# M840K.net
KiCad netlist of a schematic drawn in EAGLE
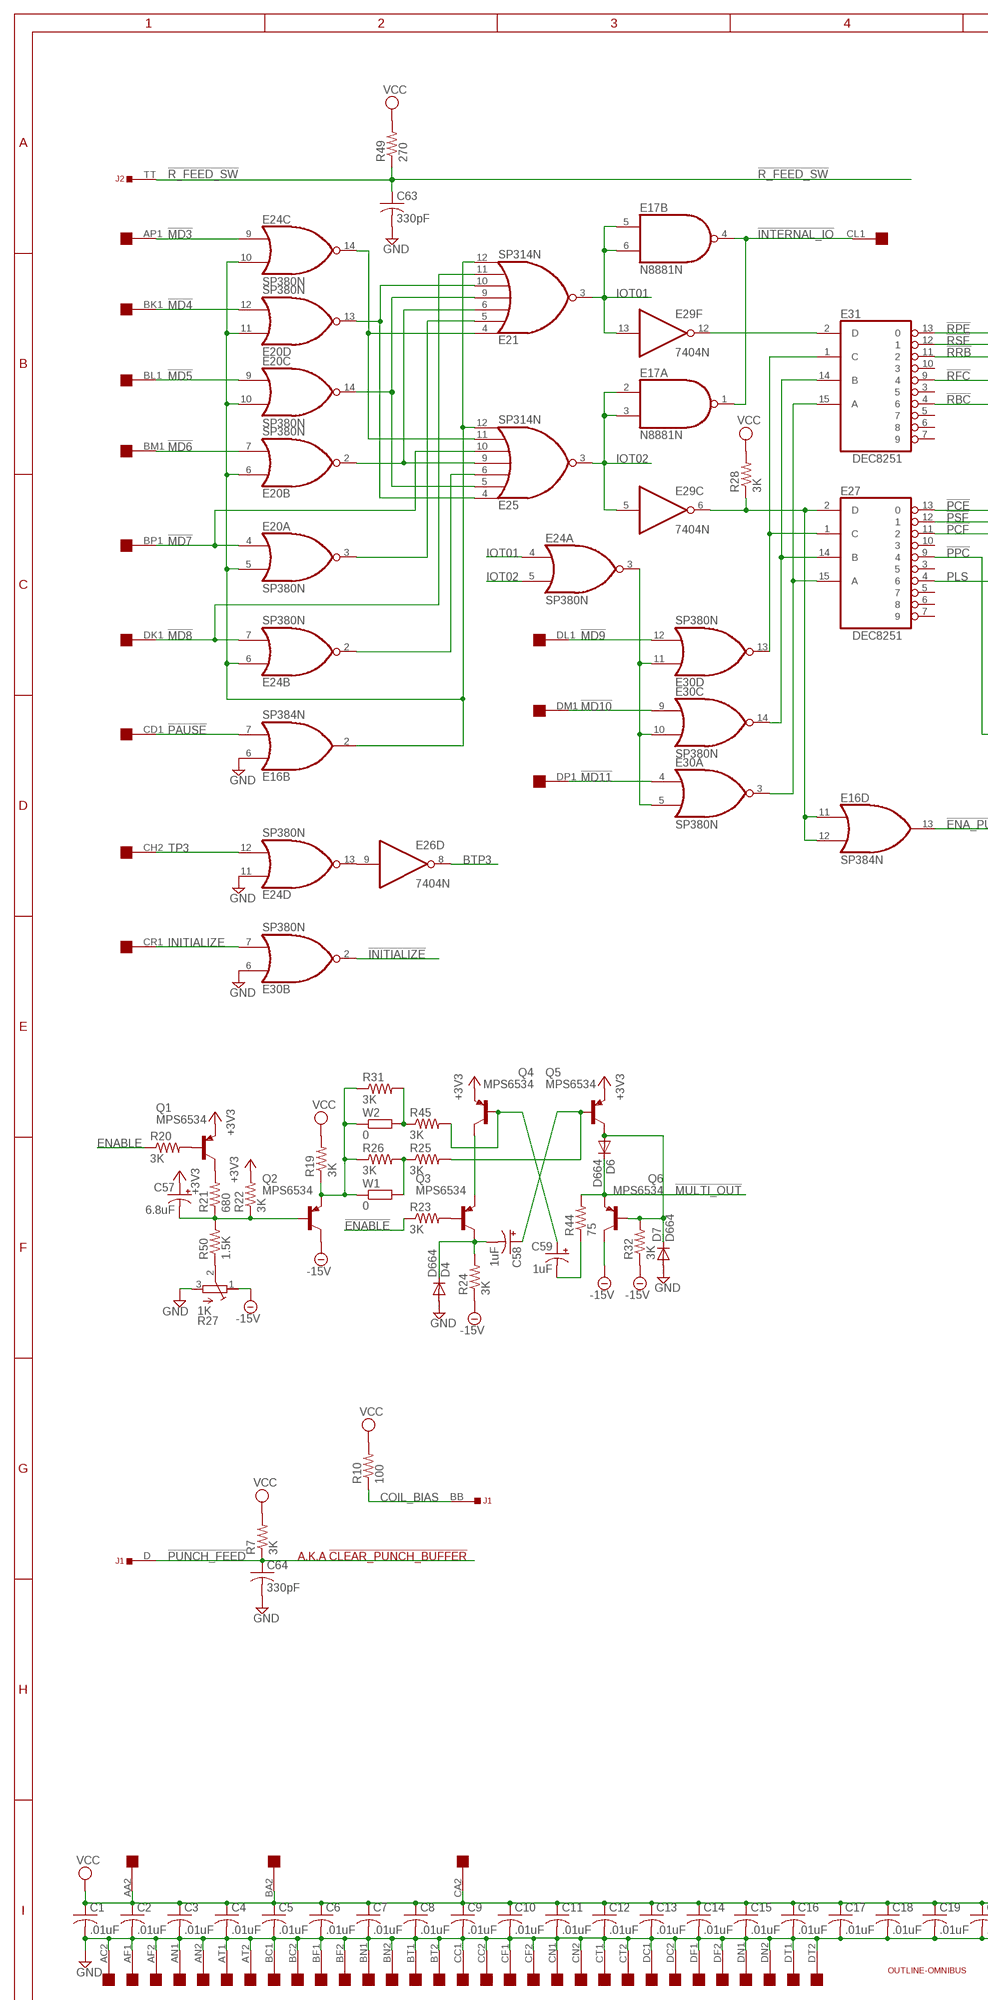
[diagram p0: schematic, sheet 1, part 1 of 2]
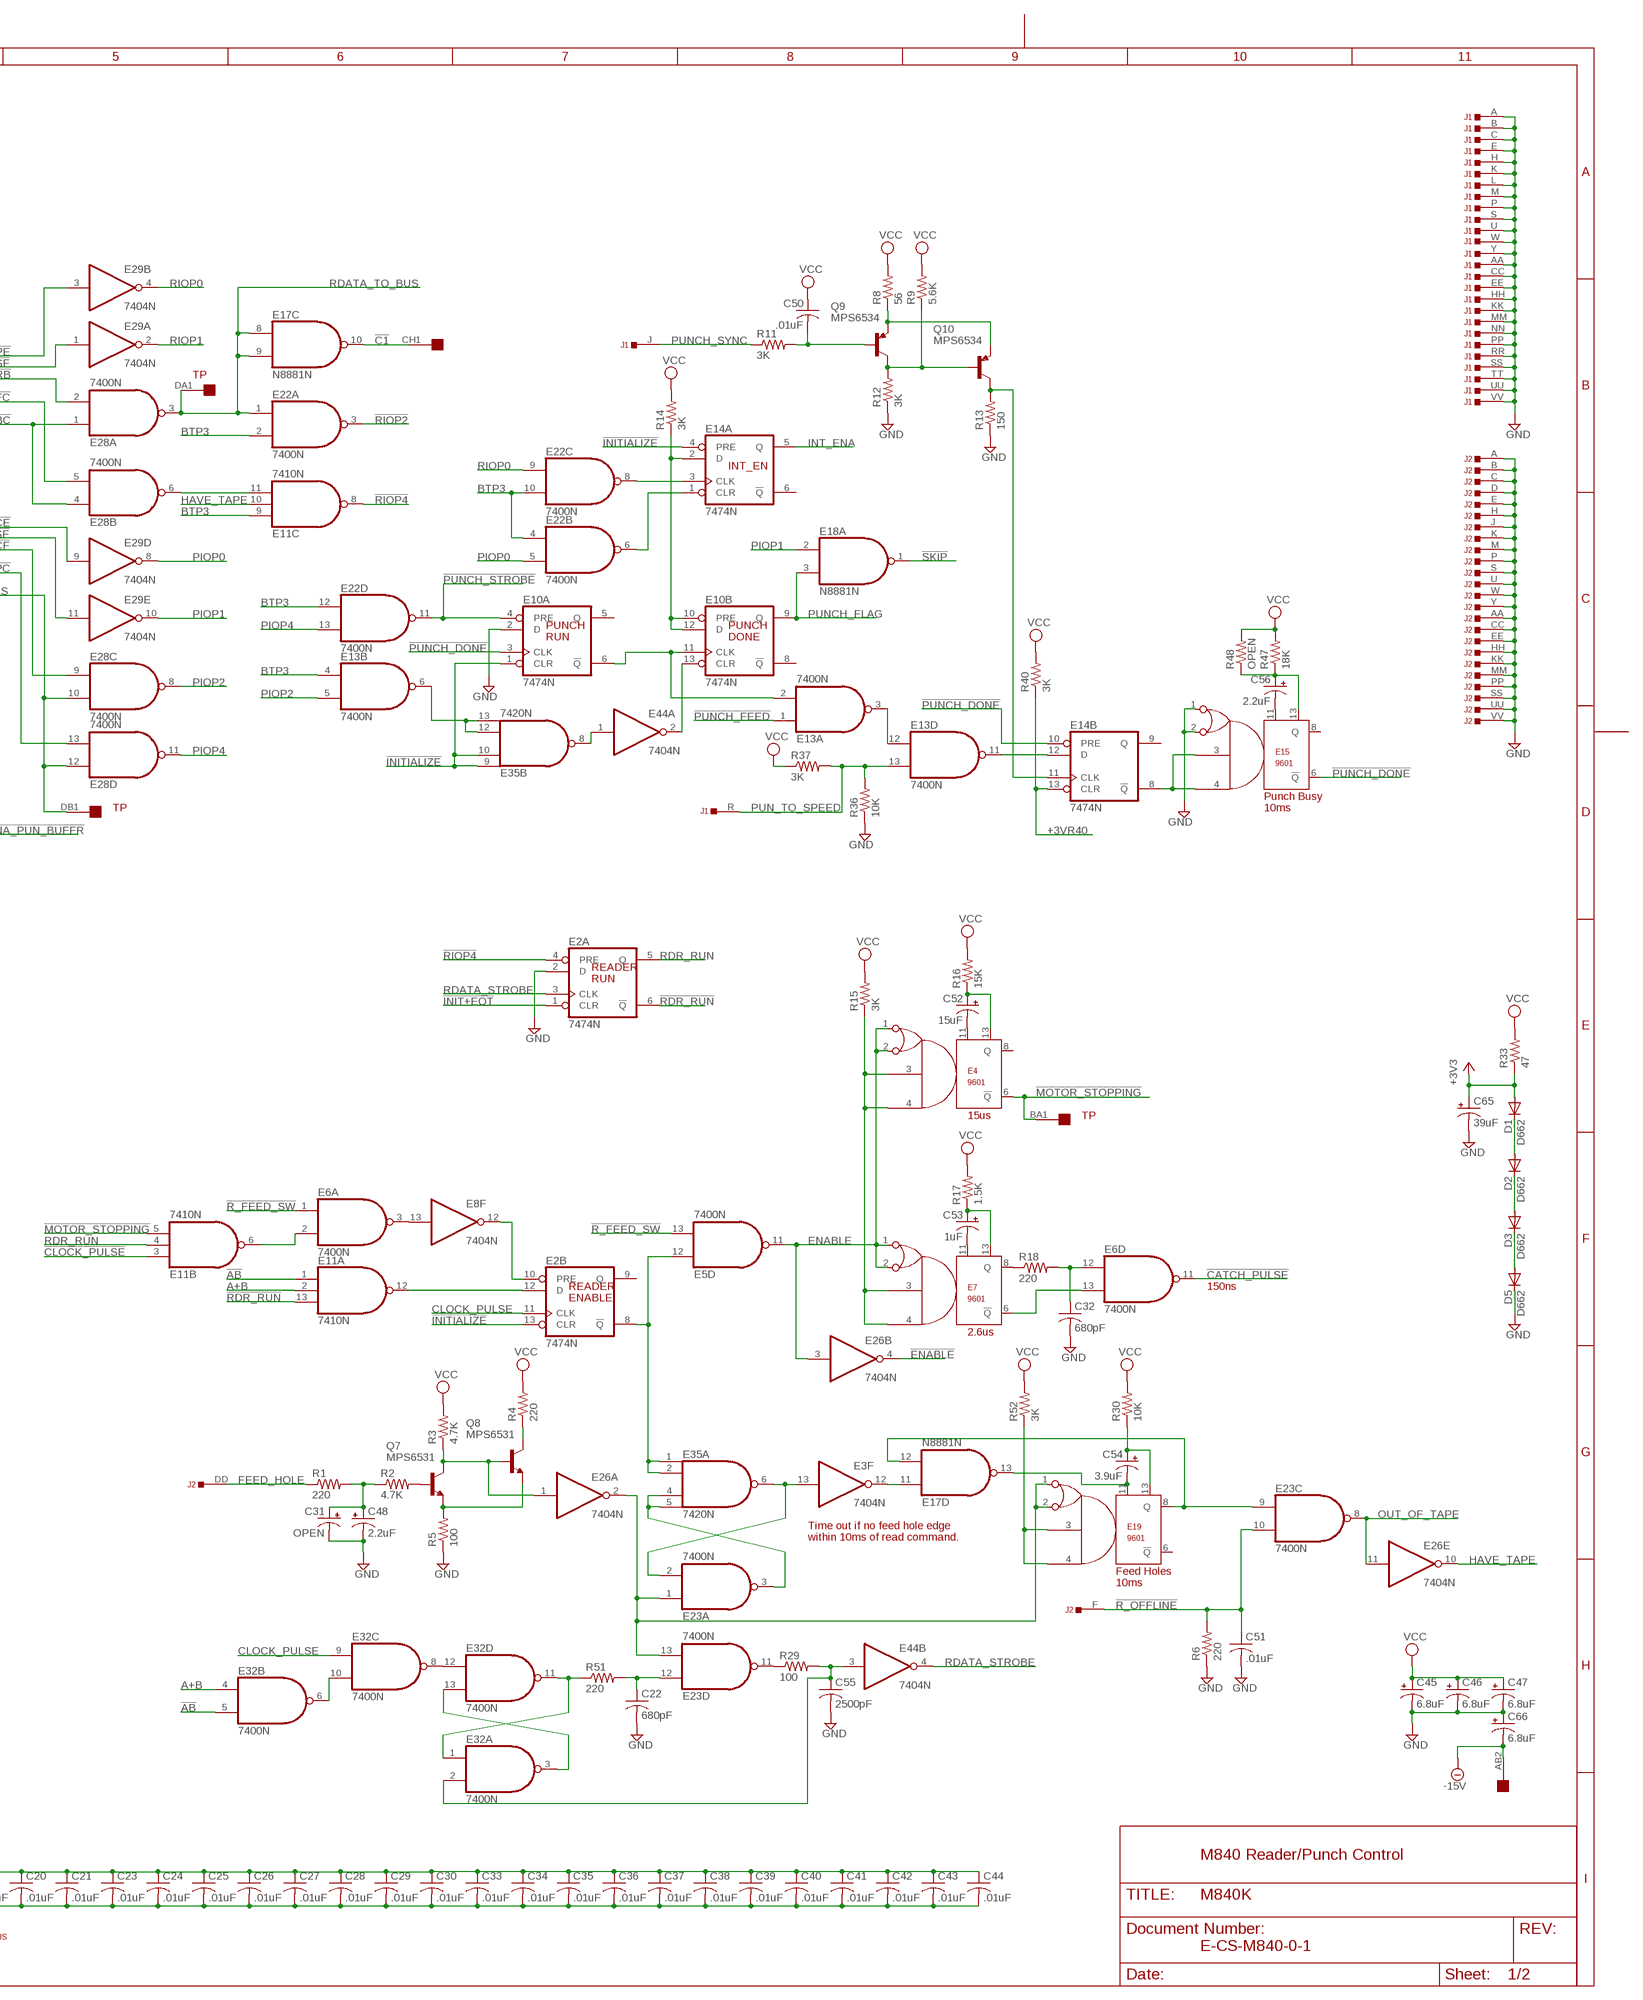
[diagram p1: schematic, sheet 1, part 2 of 2]
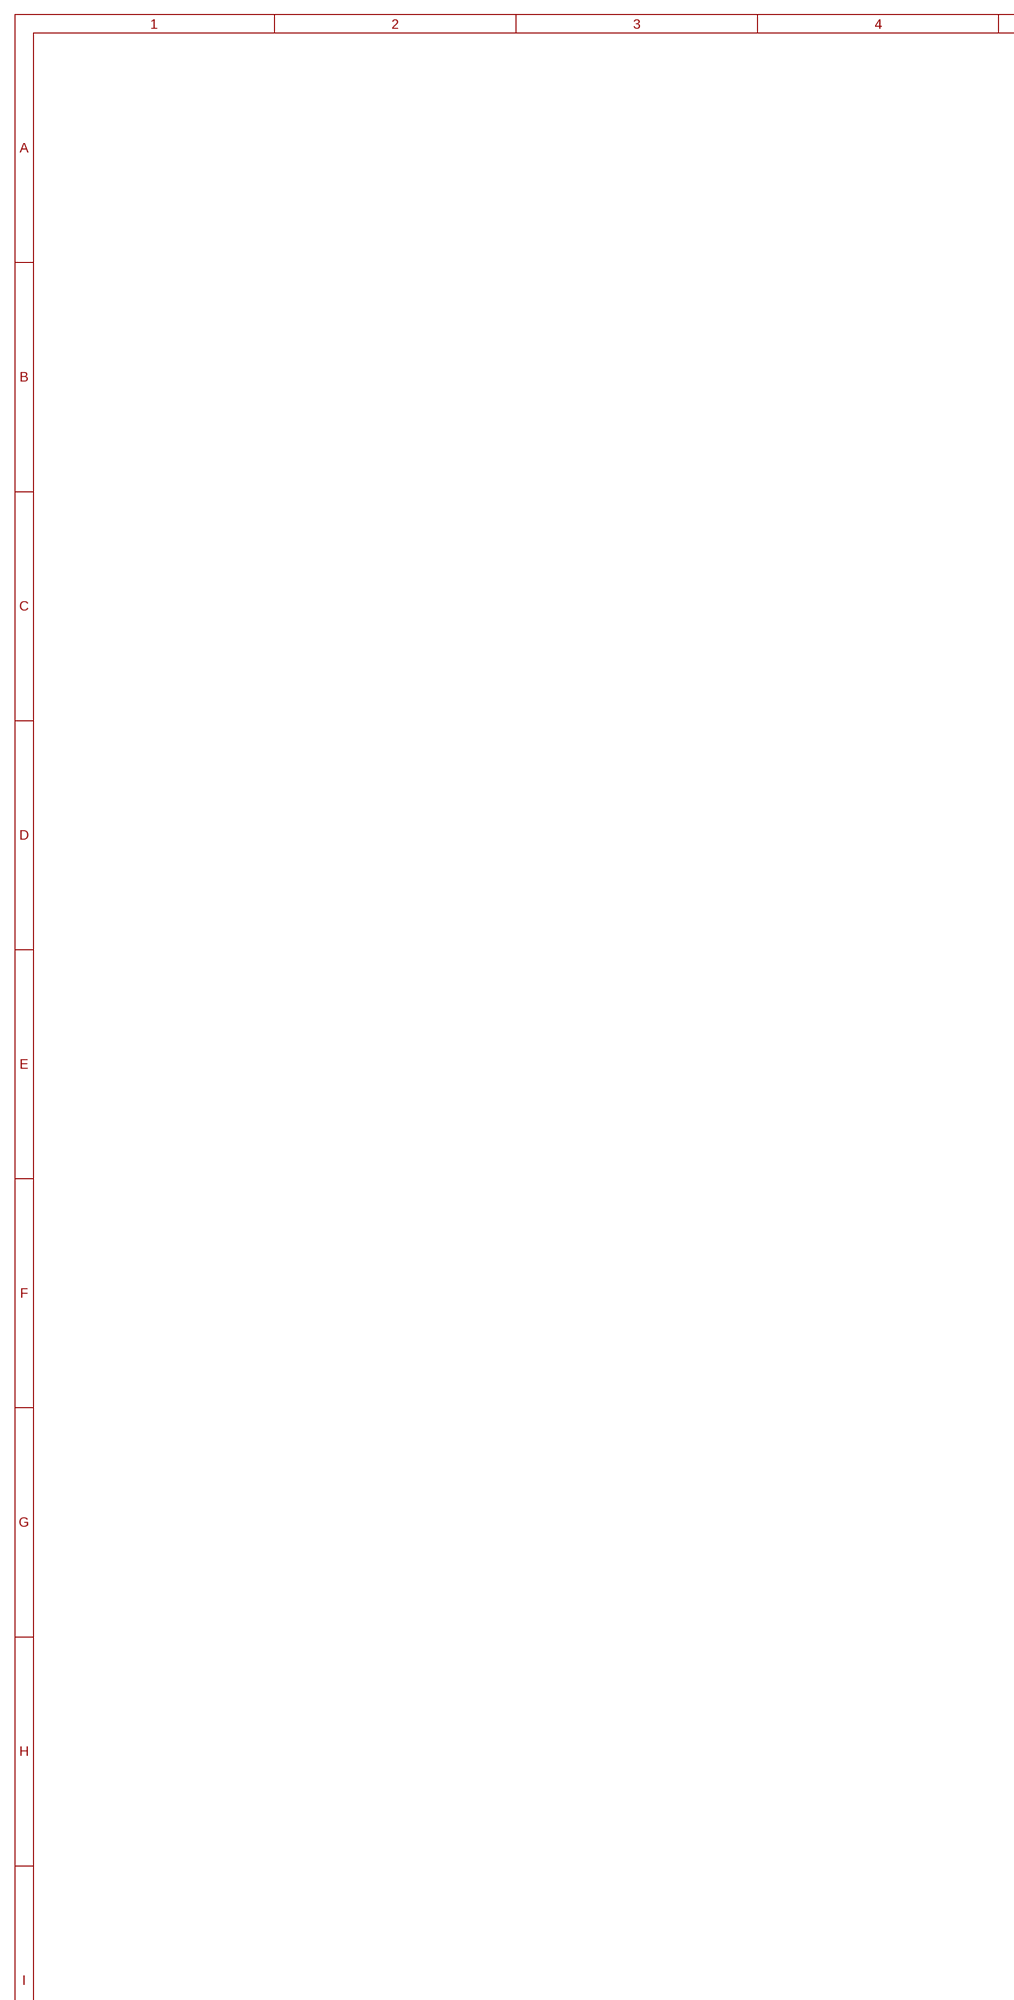
[diagram p2: schematic, sheet 2, part 1 of 2]
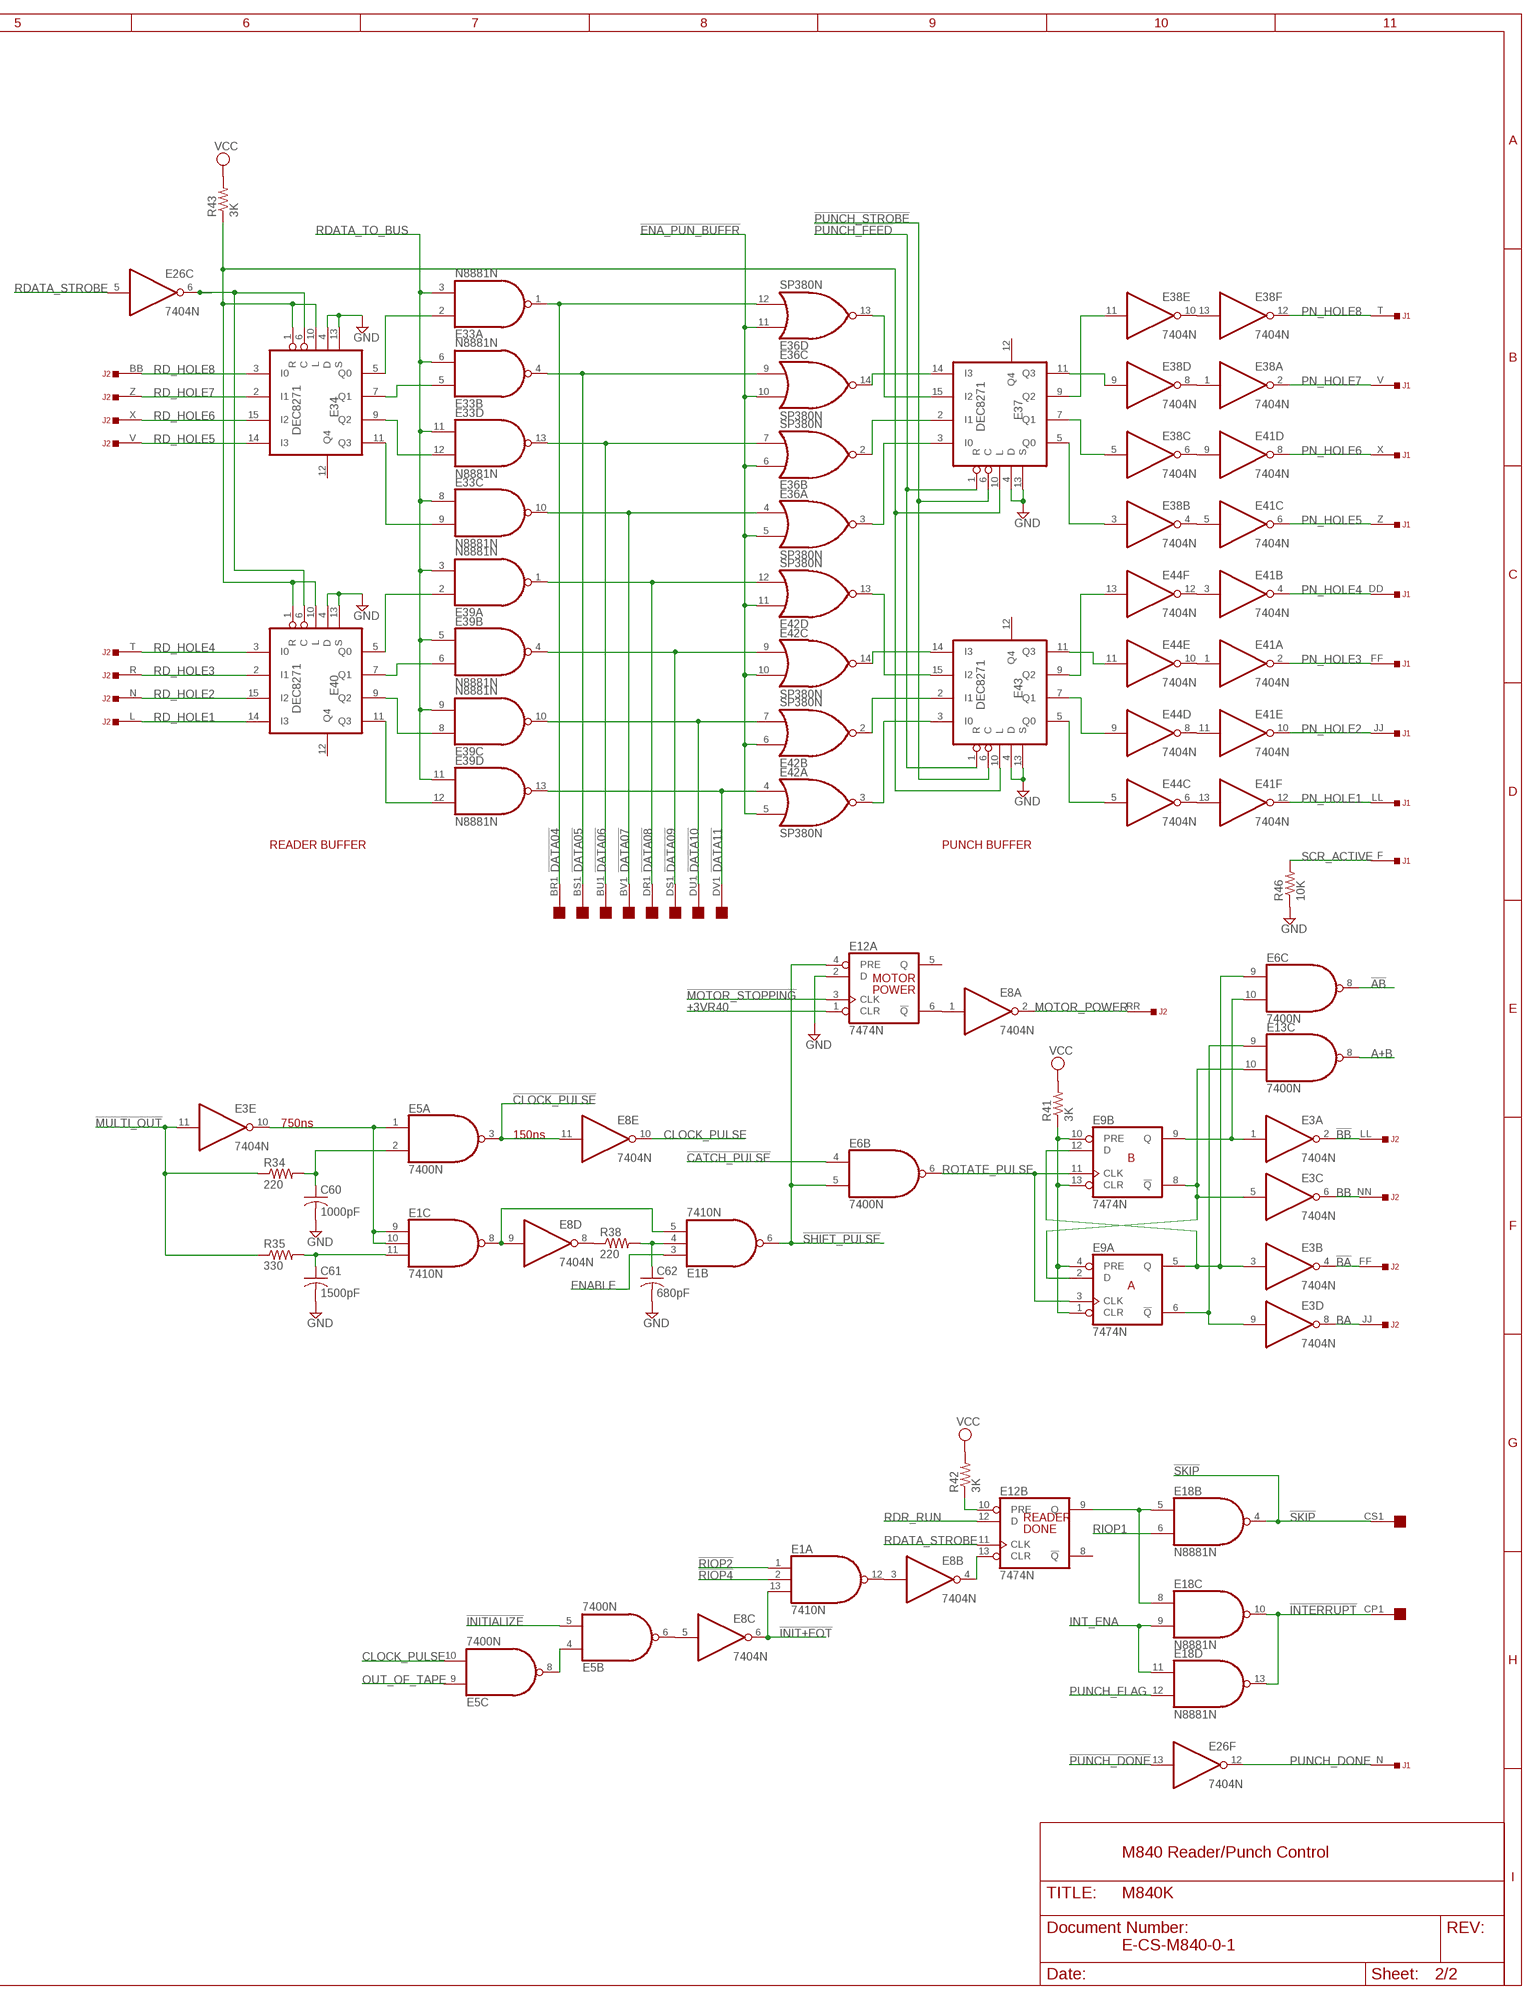
[diagram p3: schematic, sheet 2, part 2 of 2]

(export (version "E")
  (design (tool "Eeschema 10.0.6"))
  (components
    (comp (ref "C60")
      (value "1000pF")
      (footprint "eagle-import:C063-025X075")
      (libsource (lib "eagle-import") (part "C-US"))
    )
    (comp (ref "C61")
      (value "1500pF")
      (footprint "eagle-import:C063-025X075")
      (libsource (lib "eagle-import") (part "C-US"))
    )
    (comp (ref "C62")
      (value "680pF")
      (footprint "eagle-import:C063-025X075")
      (libsource (lib "eagle-import") (part "C-US"))
    )
    (comp (ref "E1")
      (value "7410N")
      (footprint "eagle-import:DIL14")
      (libsource (lib "eagle-import") (part "7410N"))
    )
    (comp (ref "E3")
      (value "7404N")
      (footprint "eagle-import:DIL14")
      (libsource (lib "eagle-import") (part "7404N"))
    )
    (comp (ref "E5")
      (value "7400N")
      (footprint "eagle-import:DIL14")
      (libsource (lib "eagle-import") (part "7400N"))
    )
    (comp (ref "E6")
      (value "7400N")
      (footprint "eagle-import:DIL14")
      (libsource (lib "eagle-import") (part "7400N"))
    )
    (comp (ref "E8")
      (value "7404N")
      (footprint "eagle-import:DIL14")
      (libsource (lib "eagle-import") (part "7404N"))
    )
    (comp (ref "E9")
      (value "7474N")
      (footprint "eagle-import:DIL14")
      (libsource (lib "eagle-import") (part "7474NS"))
    )
    (comp (ref "E12")
      (value "7474N")
      (footprint "eagle-import:DIL14")
      (libsource (lib "eagle-import") (part "7474NS"))
    )
    (comp (ref "E13")
      (value "7400N")
      (footprint "eagle-import:DIL14")
      (libsource (lib "eagle-import") (part "7400N"))
    )
    (comp (ref "E18")
      (value "N8881N")
      (footprint "eagle-import:DIL14")
      (libsource (lib "eagle-import") (part "N8881N"))
    )
    (comp (ref "E26")
      (value "7404N")
      (footprint "eagle-import:DIL14")
      (libsource (lib "eagle-import") (part "7404N"))
    )
    (comp (ref "E33")
      (value "N8881N")
      (footprint "eagle-import:DIL14")
      (libsource (lib "eagle-import") (part "N8881N"))
    )
    (comp (ref "E34")
      (value "DEC8271")
      (footprint "eagle-import:DIL16")
      (libsource (lib "eagle-import") (part "DEC8271"))
    )
    (comp (ref "E36")
      (value "SP380N")
      (footprint "eagle-import:DIL14")
      (libsource (lib "eagle-import") (part "SP380N"))
    )
    (comp (ref "E37")
      (value "DEC8271")
      (footprint "eagle-import:DIL16")
      (libsource (lib "eagle-import") (part "DEC8271"))
    )
    (comp (ref "E38")
      (value "7404N")
      (footprint "eagle-import:DIL14")
      (libsource (lib "eagle-import") (part "7404N"))
    )
    (comp (ref "E39")
      (value "N8881N")
      (footprint "eagle-import:DIL14")
      (libsource (lib "eagle-import") (part "N8881N"))
    )
    (comp (ref "E40")
      (value "DEC8271")
      (footprint "eagle-import:DIL16")
      (libsource (lib "eagle-import") (part "DEC8271"))
    )
    (comp (ref "E41")
      (value "7404N")
      (footprint "eagle-import:DIL14")
      (libsource (lib "eagle-import") (part "7404N"))
    )
    (comp (ref "E42")
      (value "SP380N")
      (footprint "eagle-import:DIL14")
      (libsource (lib "eagle-import") (part "SP380N"))
    )
    (comp (ref "E43")
      (value "DEC8271")
      (footprint "eagle-import:DIL16")
      (libsource (lib "eagle-import") (part "DEC8271"))
    )
    (comp (ref "E44")
      (value "7404N")
      (footprint "eagle-import:DIL14")
      (libsource (lib "eagle-import") (part "7404N"))
    )
    (comp (ref "J1")
      (value "DEC40PINSH")
      (footprint "eagle-import:DEC40PINH")
      (libsource (lib "eagle-import") (part "DEC40PINSH"))
    )
    (comp (ref "J2")
      (value "DEC40PINSH")
      (footprint "eagle-import:DEC40PINH")
      (libsource (lib "eagle-import") (part "DEC40PINSH"))
    )
    (comp (ref "OMNIBUS")
      (value "QUAD")
      (footprint "eagle-import:EDGE-CON8")
      (libsource (lib "eagle-import") (part "QUAD"))
    )
    (comp (ref "R34")
      (value "220")
      (footprint "eagle-import:0207_10")
      (libsource (lib "eagle-import") (part "R-US_0207/10"))
    )
    (comp (ref "R35")
      (value "330")
      (footprint "eagle-import:0207_10")
      (libsource (lib "eagle-import") (part "R-US_0207/10"))
    )
    (comp (ref "R38")
      (value "220")
      (footprint "eagle-import:0207_10")
      (libsource (lib "eagle-import") (part "R-US_0207/10"))
    )
    (comp (ref "R41")
      (value "3K")
      (footprint "eagle-import:0207_10")
      (libsource (lib "eagle-import") (part "R-US_0207/10"))
    )
    (comp (ref "R42")
      (value "3K")
      (footprint "eagle-import:0207_10")
      (libsource (lib "eagle-import") (part "R-US_0207/10"))
    )
    (comp (ref "R43")
      (value "3K")
      (footprint "eagle-import:0207_10")
      (libsource (lib "eagle-import") (part "R-US_0207/10"))
    )
    (comp (ref "R46")
      (value "10K")
      (footprint "eagle-import:0207_10")
      (libsource (lib "eagle-import") (part "R-US_0207/10"))
    )
    (comp (ref "C1")
      (value ".01uF")
      (footprint "eagle-import:C063-025X075")
      (libsource (lib "eagle-import") (part "C-US"))
    )
    (comp (ref "C2")
      (value ".01uF")
      (footprint "eagle-import:C063-025X075")
      (libsource (lib "eagle-import") (part "C-US"))
    )
    (comp (ref "C3")
      (value ".01uF")
      (footprint "eagle-import:C063-025X075")
      (libsource (lib "eagle-import") (part "C-US"))
    )
    (comp (ref "C4")
      (value ".01uF")
      (footprint "eagle-import:C063-025X075")
      (libsource (lib "eagle-import") (part "C-US"))
    )
    (comp (ref "C5")
      (value ".01uF")
      (footprint "eagle-import:C063-025X075")
      (libsource (lib "eagle-import") (part "C-US"))
    )
    (comp (ref "C6")
      (value ".01uF")
      (footprint "eagle-import:C063-025X075")
      (libsource (lib "eagle-import") (part "C-US"))
    )
    (comp (ref "C7")
      (value ".01uF")
      (footprint "eagle-import:C063-025X075")
      (libsource (lib "eagle-import") (part "C-US"))
    )
    (comp (ref "C8")
      (value ".01uF")
      (footprint "eagle-import:C063-025X075")
      (libsource (lib "eagle-import") (part "C-US"))
    )
    (comp (ref "C9")
      (value ".01uF")
      (footprint "eagle-import:C063-025X075")
      (libsource (lib "eagle-import") (part "C-US"))
    )
    (comp (ref "C10")
      (value ".01uF")
      (footprint "eagle-import:C063-025X075")
      (libsource (lib "eagle-import") (part "C-US"))
    )
    (comp (ref "C11")
      (value ".01uF")
      (footprint "eagle-import:C063-025X075")
      (libsource (lib "eagle-import") (part "C-US"))
    )
    (comp (ref "C12")
      (value ".01uF")
      (footprint "eagle-import:C063-025X075")
      (libsource (lib "eagle-import") (part "C-US"))
    )
    (comp (ref "C13")
      (value ".01uF")
      (footprint "eagle-import:C063-025X075")
      (libsource (lib "eagle-import") (part "C-US"))
    )
    (comp (ref "C14")
      (value ".01uF")
      (footprint "eagle-import:C063-025X075")
      (libsource (lib "eagle-import") (part "C-US"))
    )
    (comp (ref "C15")
      (value ".01uF")
      (footprint "eagle-import:C063-025X075")
      (libsource (lib "eagle-import") (part "C-US"))
    )
    (comp (ref "C16")
      (value ".01uF")
      (footprint "eagle-import:C063-025X075")
      (libsource (lib "eagle-import") (part "C-US"))
    )
    (comp (ref "C17")
      (value ".01uF")
      (footprint "eagle-import:C063-025X075")
      (libsource (lib "eagle-import") (part "C-US"))
    )
    (comp (ref "C18")
      (value ".01uF")
      (footprint "eagle-import:C063-025X075")
      (libsource (lib "eagle-import") (part "C-US"))
    )
    (comp (ref "C19")
      (value ".01uF")
      (footprint "eagle-import:C063-025X075")
      (libsource (lib "eagle-import") (part "C-US"))
    )
    (comp (ref "C20")
      (value ".01uF")
      (footprint "eagle-import:C063-025X075")
      (libsource (lib "eagle-import") (part "C-US"))
    )
    (comp (ref "C21")
      (value ".01uF")
      (footprint "eagle-import:C063-025X075")
      (libsource (lib "eagle-import") (part "C-US"))
    )
    (comp (ref "C22")
      (value "680pF")
      (footprint "eagle-import:C063-025X075")
      (libsource (lib "eagle-import") (part "C-US"))
    )
    (comp (ref "C23")
      (value ".01uF")
      (footprint "eagle-import:C063-025X075")
      (libsource (lib "eagle-import") (part "C-US"))
    )
    (comp (ref "C24")
      (value ".01uF")
      (footprint "eagle-import:C063-025X075")
      (libsource (lib "eagle-import") (part "C-US"))
    )
    (comp (ref "C25")
      (value ".01uF")
      (footprint "eagle-import:C063-025X075")
      (libsource (lib "eagle-import") (part "C-US"))
    )
    (comp (ref "C26")
      (value ".01uF")
      (footprint "eagle-import:C063-025X075")
      (libsource (lib "eagle-import") (part "C-US"))
    )
    (comp (ref "C27")
      (value ".01uF")
      (footprint "eagle-import:C063-025X075")
      (libsource (lib "eagle-import") (part "C-US"))
    )
    (comp (ref "C28")
      (value ".01uF")
      (footprint "eagle-import:C063-025X075")
      (libsource (lib "eagle-import") (part "C-US"))
    )
    (comp (ref "C29")
      (value ".01uF")
      (footprint "eagle-import:C063-025X075")
      (libsource (lib "eagle-import") (part "C-US"))
    )
    (comp (ref "C30")
      (value ".01uF")
      (footprint "eagle-import:C063-025X075")
      (libsource (lib "eagle-import") (part "C-US"))
    )
    (comp (ref "C31")
      (value "OPEN")
      (footprint "eagle-import:E15-5")
      (libsource (lib "eagle-import") (part "CPOL-USE15-5AXIAL"))
    )
    (comp (ref "C32")
      (value "680pF")
      (footprint "eagle-import:C063-025X075")
      (libsource (lib "eagle-import") (part "C-US"))
    )
    (comp (ref "C33")
      (value ".01uF")
      (footprint "eagle-import:C063-025X075")
      (libsource (lib "eagle-import") (part "C-US"))
    )
    (comp (ref "C34")
      (value ".01uF")
      (footprint "eagle-import:C063-025X075")
      (libsource (lib "eagle-import") (part "C-US"))
    )
    (comp (ref "C35")
      (value ".01uF")
      (footprint "eagle-import:C063-025X075")
      (libsource (lib "eagle-import") (part "C-US"))
    )
    (comp (ref "C36")
      (value ".01uF")
      (footprint "eagle-import:C063-025X075")
      (libsource (lib "eagle-import") (part "C-US"))
    )
    (comp (ref "C37")
      (value ".01uF")
      (footprint "eagle-import:C063-025X075")
      (libsource (lib "eagle-import") (part "C-US"))
    )
    (comp (ref "C38")
      (value ".01uF")
      (footprint "eagle-import:C063-025X075")
      (libsource (lib "eagle-import") (part "C-US"))
    )
    (comp (ref "C39")
      (value ".01uF")
      (footprint "eagle-import:C063-025X075")
      (libsource (lib "eagle-import") (part "C-US"))
    )
    (comp (ref "C40")
      (value ".01uF")
      (footprint "eagle-import:C063-025X075")
      (libsource (lib "eagle-import") (part "C-US"))
    )
    (comp (ref "C41")
      (value ".01uF")
      (footprint "eagle-import:C063-025X075")
      (libsource (lib "eagle-import") (part "C-US"))
    )
    (comp (ref "C42")
      (value ".01uF")
      (footprint "eagle-import:C063-025X075")
      (libsource (lib "eagle-import") (part "C-US"))
    )
    (comp (ref "C43")
      (value ".01uF")
      (footprint "eagle-import:C063-025X075")
      (libsource (lib "eagle-import") (part "C-US"))
    )
    (comp (ref "C44")
      (value ".01uF")
      (footprint "eagle-import:C063-025X075")
      (libsource (lib "eagle-import") (part "C-US"))
    )
    (comp (ref "C45")
      (value "6.8uF")
      (footprint "eagle-import:E12-8")
      (libsource (lib "eagle-import") (part "CPOL-USE20-8AXIAL"))
    )
    (comp (ref "C46")
      (value "6.8uF")
      (footprint "eagle-import:E12-8")
      (libsource (lib "eagle-import") (part "CPOL-USE20-8AXIAL"))
    )
    (comp (ref "C47")
      (value "6.8uF")
      (footprint "eagle-import:E12-8")
      (libsource (lib "eagle-import") (part "CPOL-USE20-8AXIAL"))
    )
    (comp (ref "C48")
      (value "2.2uF")
      (footprint "eagle-import:E15-5")
      (libsource (lib "eagle-import") (part "CPOL-USE15-5AXIAL"))
    )
    (comp (ref "C50")
      (value ".01uF")
      (footprint "eagle-import:C203-054-229")
      (libsource (lib "eagle-import") (part "C-US8"))
    )
    (comp (ref "C51")
      (value ".01uF")
      (footprint "eagle-import:C203-054-229")
      (libsource (lib "eagle-import") (part "C-US8"))
    )
    (comp (ref "C52")
      (value "15uF")
      (footprint "eagle-import:E12-8")
      (libsource (lib "eagle-import") (part "CPOL-USE20-8AXIAL"))
    )
    (comp (ref "C53")
      (value "1uF")
      (footprint "eagle-import:E15-5")
      (libsource (lib "eagle-import") (part "CPOL-USE15-5AXIAL"))
    )
    (comp (ref "C54")
      (value "3.9uF")
      (footprint "eagle-import:E15-5")
      (libsource (lib "eagle-import") (part "CPOL-USE15-5AXIAL"))
    )
    (comp (ref "C55")
      (value "2500pF")
      (footprint "eagle-import:C063-025X075")
      (libsource (lib "eagle-import") (part "C-US"))
    )
    (comp (ref "C56")
      (value "2.2uF")
      (footprint "eagle-import:E15-5")
      (libsource (lib "eagle-import") (part "CPOL-USE15-5AXIAL"))
    )
    (comp (ref "C57")
      (value "6.8uF")
      (footprint "eagle-import:E12-8")
      (libsource (lib "eagle-import") (part "CPOL-USE20-8AXIAL"))
    )
    (comp (ref "C58")
      (value "1uF")
      (footprint "eagle-import:E15-5")
      (libsource (lib "eagle-import") (part "CPOL-USE15-5AXIAL"))
    )
    (comp (ref "C59")
      (value "1uF")
      (footprint "eagle-import:E15-5")
      (libsource (lib "eagle-import") (part "CPOL-USE15-5AXIAL"))
    )
    (comp (ref "C63")
      (value "330pF")
      (footprint "eagle-import:C063-025X075")
      (libsource (lib "eagle-import") (part "C-US"))
    )
    (comp (ref "C64")
      (value "330pF")
      (footprint "eagle-import:C063-025X075")
      (libsource (lib "eagle-import") (part "C-US"))
    )
    (comp (ref "C65")
      (value "39uF")
      (footprint "eagle-import:E12-8")
      (libsource (lib "eagle-import") (part "CPOL-USE20-8AXIAL"))
    )
    (comp (ref "C66")
      (value "6.8uF")
      (footprint "eagle-import:E12-8")
      (libsource (lib "eagle-import") (part "CPOL-USE20-8AXIAL"))
    )
    (comp (ref "D1")
      (value "D662")
      (footprint "eagle-import:DO35-10")
      (libsource (lib "eagle-import") (part "DIODE-DO35-10"))
    )
    (comp (ref "D2")
      (value "D662")
      (footprint "eagle-import:DO35-10")
      (libsource (lib "eagle-import") (part "DIODE-DO35-10"))
    )
    (comp (ref "D3")
      (value "D662")
      (footprint "eagle-import:DO35-10")
      (libsource (lib "eagle-import") (part "DIODE-DO35-10"))
    )
    (comp (ref "D4")
      (value "D664")
      (footprint "eagle-import:DO35-10")
      (libsource (lib "eagle-import") (part "DIODE-DO35-10"))
    )
    (comp (ref "D5")
      (value "D662")
      (footprint "eagle-import:DO35-10")
      (libsource (lib "eagle-import") (part "DIODE-DO35-10"))
    )
    (comp (ref "D6")
      (value "D664")
      (footprint "eagle-import:DO35-10")
      (libsource (lib "eagle-import") (part "DIODE-DO35-10"))
    )
    (comp (ref "D7")
      (value "D664")
      (footprint "eagle-import:DO35-10")
      (libsource (lib "eagle-import") (part "DIODE-DO35-10"))
    )
    (comp (ref "E2")
      (value "7474N")
      (footprint "eagle-import:DIL14")
      (libsource (lib "eagle-import") (part "7474NS"))
    )
    (comp (ref "E4")
      (value "9601")
      (footprint "eagle-import:DIL14")
      (libsource (lib "eagle-import") (part "9601"))
    )
    (comp (ref "E7")
      (value "9601")
      (footprint "eagle-import:DIL14")
      (libsource (lib "eagle-import") (part "9601"))
    )
    (comp (ref "E10")
      (value "7474N")
      (footprint "eagle-import:DIL14")
      (libsource (lib "eagle-import") (part "7474NS"))
    )
    (comp (ref "E11")
      (value "7410N")
      (footprint "eagle-import:DIL14")
      (libsource (lib "eagle-import") (part "7410N"))
    )
    (comp (ref "E14")
      (value "7474N")
      (footprint "eagle-import:DIL14")
      (libsource (lib "eagle-import") (part "7474NS"))
    )
    (comp (ref "E15")
      (value "9601")
      (footprint "eagle-import:DIL14")
      (libsource (lib "eagle-import") (part "9601"))
    )
    (comp (ref "E16")
      (value "SP384N")
      (footprint "eagle-import:DIL14")
      (libsource (lib "eagle-import") (part "SP384N"))
    )
    (comp (ref "E17")
      (value "N8881N")
      (footprint "eagle-import:DIL14")
      (libsource (lib "eagle-import") (part "N8881N"))
    )
    (comp (ref "E19")
      (value "9601")
      (footprint "eagle-import:DIL14")
      (libsource (lib "eagle-import") (part "9601"))
    )
    (comp (ref "E20")
      (value "SP380N")
      (footprint "eagle-import:DIL14")
      (libsource (lib "eagle-import") (part "SP380N"))
    )
    (comp (ref "E21")
      (value "SP314N")
      (footprint "eagle-import:DIL14")
      (libsource (lib "eagle-import") (part "SP314N"))
    )
    (comp (ref "E22")
      (value "7400N")
      (footprint "eagle-import:DIL14")
      (libsource (lib "eagle-import") (part "7400N"))
    )
    (comp (ref "E23")
      (value "7400N")
      (footprint "eagle-import:DIL14")
      (libsource (lib "eagle-import") (part "7400N"))
    )
    (comp (ref "E24")
      (value "SP380N")
      (footprint "eagle-import:DIL14")
      (libsource (lib "eagle-import") (part "SP380N"))
    )
    (comp (ref "E25")
      (value "SP314N")
      (footprint "eagle-import:DIL14")
      (libsource (lib "eagle-import") (part "SP314N"))
    )
    (comp (ref "E27")
      (value "DEC8251")
      (footprint "eagle-import:DIL16")
      (libsource (lib "eagle-import") (part "DEC8251"))
    )
    (comp (ref "E28")
      (value "7400N")
      (footprint "eagle-import:DIL14")
      (libsource (lib "eagle-import") (part "7400N"))
    )
    (comp (ref "E29")
      (value "7404N")
      (footprint "eagle-import:DIL14")
      (libsource (lib "eagle-import") (part "7404N"))
    )
    (comp (ref "E30")
      (value "SP380N")
      (footprint "eagle-import:DIL14")
      (libsource (lib "eagle-import") (part "SP380N"))
    )
    (comp (ref "E31")
      (value "DEC8251")
      (footprint "eagle-import:DIL16")
      (libsource (lib "eagle-import") (part "DEC8251"))
    )
    (comp (ref "E32")
      (value "7400N")
      (footprint "eagle-import:DIL14")
      (libsource (lib "eagle-import") (part "7400N"))
    )
    (comp (ref "E35")
      (value "7420N")
      (footprint "eagle-import:DIL14")
      (libsource (lib "eagle-import") (part "7420N"))
    )
    (comp (ref "Q1")
      (value "MPS6534")
      (footprint "eagle-import:TO5")
      (libsource (lib "eagle-import") (part "-PNP-TO5"))
    )
    (comp (ref "Q2")
      (value "MPS6534")
      (footprint "eagle-import:TO5")
      (libsource (lib "eagle-import") (part "-PNP-TO5"))
    )
    (comp (ref "Q3")
      (value "MPS6534")
      (footprint "eagle-import:TO5")
      (libsource (lib "eagle-import") (part "-PNP-TO5"))
    )
    (comp (ref "Q4")
      (value "MPS6534")
      (footprint "eagle-import:TO5")
      (libsource (lib "eagle-import") (part "-PNP-TO5"))
    )
    (comp (ref "Q5")
      (value "MPS6534")
      (footprint "eagle-import:TO5")
      (libsource (lib "eagle-import") (part "-PNP-TO5"))
    )
    (comp (ref "Q6")
      (value "MPS6534")
      (footprint "eagle-import:TO5")
      (libsource (lib "eagle-import") (part "-PNP-TO5"))
    )
    (comp (ref "Q7")
      (value "MPS6531")
      (footprint "eagle-import:TO5")
      (libsource (lib "eagle-import") (part "-NPN-TO5"))
    )
    (comp (ref "Q8")
      (value "MPS6531")
      (footprint "eagle-import:TO5")
      (libsource (lib "eagle-import") (part "-NPN-TO5"))
    )
    (comp (ref "Q9")
      (value "MPS6534")
      (footprint "eagle-import:TO5")
      (libsource (lib "eagle-import") (part "-PNP-TO5"))
    )
    (comp (ref "Q10")
      (value "MPS6534")
      (footprint "eagle-import:TO5")
      (libsource (lib "eagle-import") (part "-PNP-TO5"))
    )
    (comp (ref "R1")
      (value "220")
      (footprint "eagle-import:0207_10")
      (libsource (lib "eagle-import") (part "R-US_0207/10"))
    )
    (comp (ref "R2")
      (value "4.7K")
      (footprint "eagle-import:0207_10")
      (libsource (lib "eagle-import") (part "R-US_0207/10"))
    )
    (comp (ref "R3")
      (value "4.7K")
      (footprint "eagle-import:0207_10")
      (libsource (lib "eagle-import") (part "R-US_0207/10"))
    )
    (comp (ref "R4")
      (value "220")
      (footprint "eagle-import:0207_10")
      (libsource (lib "eagle-import") (part "R-US_0207/10"))
    )
    (comp (ref "R5")
      (value "100")
      (footprint "eagle-import:0207_10")
      (libsource (lib "eagle-import") (part "R-US_0207/10"))
    )
    (comp (ref "R6")
      (value "220")
      (footprint "eagle-import:0207_10")
      (libsource (lib "eagle-import") (part "R-US_0207/10"))
    )
    (comp (ref "R7")
      (value "3K")
      (footprint "eagle-import:0207_10")
      (libsource (lib "eagle-import") (part "R-US_0207/10"))
    )
    (comp (ref "R8")
      (value "56")
      (footprint "eagle-import:0207_10")
      (libsource (lib "eagle-import") (part "R-US_0207/10"))
    )
    (comp (ref "R9")
      (value "5.6K")
      (footprint "eagle-import:0207_10")
      (libsource (lib "eagle-import") (part "R-US_0207/10"))
    )
    (comp (ref "R10")
      (value "100")
      (footprint "eagle-import:0207_10")
      (libsource (lib "eagle-import") (part "R-US_0207/10"))
    )
    (comp (ref "R11")
      (value "3K")
      (footprint "eagle-import:0207_10")
      (libsource (lib "eagle-import") (part "R-US_0207/10"))
    )
    (comp (ref "R12")
      (value "3K")
      (footprint "eagle-import:0207_10")
      (libsource (lib "eagle-import") (part "R-US_0207/10"))
    )
    (comp (ref "R13")
      (value "150")
      (footprint "eagle-import:0207_10")
      (libsource (lib "eagle-import") (part "R-US_0207/10"))
    )
    (comp (ref "R14")
      (value "3K")
      (footprint "eagle-import:0207_10")
      (libsource (lib "eagle-import") (part "R-US_0207/10"))
    )
    (comp (ref "R15")
      (value "3K")
      (footprint "eagle-import:0207_10")
      (libsource (lib "eagle-import") (part "R-US_0207/10"))
    )
    (comp (ref "R16")
      (value "15K")
      (footprint "eagle-import:0207_10")
      (libsource (lib "eagle-import") (part "R-US_0207/10"))
    )
    (comp (ref "R17")
      (value "1.5K")
      (footprint "eagle-import:0207_10")
      (libsource (lib "eagle-import") (part "R-US_0207/10"))
    )
    (comp (ref "R18")
      (value "220")
      (footprint "eagle-import:0207_10")
      (libsource (lib "eagle-import") (part "R-US_0207/10"))
    )
    (comp (ref "R19")
      (value "3K")
      (footprint "eagle-import:0207_10")
      (libsource (lib "eagle-import") (part "R-US_0207/10"))
    )
    (comp (ref "R20")
      (value "3K")
      (footprint "eagle-import:0207_10")
      (libsource (lib "eagle-import") (part "R-US_0207/10"))
    )
    (comp (ref "R21")
      (value "680")
      (footprint "eagle-import:0207_10")
      (libsource (lib "eagle-import") (part "R-US_0207/10"))
    )
    (comp (ref "R22")
      (value "3K")
      (footprint "eagle-import:0207_10")
      (libsource (lib "eagle-import") (part "R-US_0207/10"))
    )
    (comp (ref "R23")
      (value "3K")
      (footprint "eagle-import:0207_10")
      (libsource (lib "eagle-import") (part "R-US_0207/10"))
    )
    (comp (ref "R24")
      (value "3K")
      (footprint "eagle-import:0207_10")
      (libsource (lib "eagle-import") (part "R-US_0207/10"))
    )
    (comp (ref "R25")
      (value "3K")
      (footprint "eagle-import:0207_10")
      (libsource (lib "eagle-import") (part "R-US_0207/10"))
    )
    (comp (ref "R26")
      (value "3K")
      (footprint "eagle-import:0207_10")
      (libsource (lib "eagle-import") (part "R-US_0207/10"))
    )
    (comp (ref "R27")
      (value "1K")
      (footprint "eagle-import:3006Y")
      (libsource (lib "eagle-import") (part "275P"))
    )
    (comp (ref "R28")
      (value "3K")
      (footprint "eagle-import:0207_10")
      (libsource (lib "eagle-import") (part "R-US_0207/10"))
    )
    (comp (ref "R29")
      (value "100")
      (footprint "eagle-import:0207_10")
      (libsource (lib "eagle-import") (part "R-US_0207/10"))
    )
    (comp (ref "R30")
      (value "10K")
      (footprint "eagle-import:0207_10")
      (libsource (lib "eagle-import") (part "R-US_0207/10"))
    )
    (comp (ref "R31")
      (value "3K")
      (footprint "eagle-import:0207_10")
      (libsource (lib "eagle-import") (part "R-US_0207/10"))
    )
    (comp (ref "R32")
      (value "3K")
      (footprint "eagle-import:0207_10")
      (libsource (lib "eagle-import") (part "R-US_0207/10"))
    )
    (comp (ref "R33")
      (value "47")
      (footprint "eagle-import:0207_10")
      (libsource (lib "eagle-import") (part "R-US_0207/10"))
    )
    (comp (ref "R36")
      (value "10K")
      (footprint "eagle-import:0207_10")
      (libsource (lib "eagle-import") (part "R-US_0207/10"))
    )
    (comp (ref "R37")
      (value "3K")
      (footprint "eagle-import:0207_10")
      (libsource (lib "eagle-import") (part "R-US_0207/10"))
    )
    (comp (ref "R40")
      (value "3K")
      (footprint "eagle-import:0207_10")
      (libsource (lib "eagle-import") (part "R-US_0207/10"))
    )
    (comp (ref "R44")
      (value "75")
      (footprint "eagle-import:0207_10")
      (libsource (lib "eagle-import") (part "R-US_0207/10"))
    )
    (comp (ref "R45")
      (value "3K")
      (footprint "eagle-import:0207_10")
      (libsource (lib "eagle-import") (part "R-US_0207/10"))
    )
    (comp (ref "R47")
      (value "18K")
      (footprint "eagle-import:0207_10")
      (libsource (lib "eagle-import") (part "R-US_0207/10"))
    )
    (comp (ref "R48")
      (value "OPEN")
      (footprint "eagle-import:0207_10")
      (libsource (lib "eagle-import") (part "R-US_0207/10"))
    )
    (comp (ref "R49")
      (value "270")
      (footprint "eagle-import:0207_10")
      (libsource (lib "eagle-import") (part "R-US_0207/10"))
    )
    (comp (ref "R50")
      (value "1.5K")
      (footprint "eagle-import:0207_10")
      (libsource (lib "eagle-import") (part "R-US_0207/10"))
    )
    (comp (ref "R51")
      (value "220")
      (footprint "eagle-import:0207_10")
      (libsource (lib "eagle-import") (part "R-US_0207/10"))
    )
    (comp (ref "R52")
      (value "3K")
      (footprint "eagle-import:0207_10")
      (libsource (lib "eagle-import") (part "R-US_0207/10"))
    )
    (comp (ref "U$1")
      (value "OUTLINE-OMNIBUS")
      (footprint "eagle-import:OMNIBUS")
      (libsource (lib "eagle-import") (part "OUTLINE-OMNIBUS"))
    )
    (comp (ref "W1")
      (value "0")
      (footprint "eagle-import:0207_10")
      (libsource (lib "eagle-import") (part "R-EU_0207/10"))
    )
    (comp (ref "W2")
      (value "0")
      (footprint "eagle-import:0207_10")
      (libsource (lib "eagle-import") (part "R-EU_0207/10"))
    )
  )
  (nets
    (net (code "1") (name "+3V3") (class "Default")
      (node (ref "C57") (pin "+") (pinfunction "+_+") (pintype "passive"))
      (node (ref "C65") (pin "+") (pinfunction "+_+") (pintype "passive"))
      (node (ref "D1") (pin "A") (pinfunction "A_A") (pintype "passive"))
      (node (ref "Q1") (pin "1") (pinfunction "E_1") (pintype "passive"))
      (node (ref "Q4") (pin "1") (pinfunction "E_1") (pintype "passive"))
      (node (ref "Q5") (pin "1") (pinfunction "E_1") (pintype "passive"))
      (node (ref "R22") (pin "2") (pinfunction "2_2") (pintype "passive"))
      (node (ref "R33") (pin "1") (pinfunction "1_1") (pintype "passive"))
    )
    (net (code "2") (name "+3VR40") (class "Default")
      (node (ref "E12") (pin "1") (pinfunction "CLR_1") (pintype "input"))
      (node (ref "E14") (pin "13") (pinfunction "CLR_13") (pintype "input"))
      (node (ref "R40") (pin "1") (pinfunction "1_1") (pintype "passive"))
    )
    (net (code "3") (name "-15V") (class "Default")
      (node (ref "C66") (pin "-") (pinfunction "-_-") (pintype "passive"))
      (node (ref "OMNIBUS") (pin "AB2") (pinfunction "1_AB2") (pintype "bidirectional"))
      (node (ref "Q2") (pin "3") (pinfunction "C_3") (pintype "passive"))
      (node (ref "Q6") (pin "3") (pinfunction "C_3") (pintype "passive"))
      (node (ref "R24") (pin "1") (pinfunction "1_1") (pintype "passive"))
      (node (ref "R27") (pin "1") (pinfunction "A_1") (pintype "passive"))
      (node (ref "R32") (pin "1") (pinfunction "1_1") (pintype "passive"))
    )
    (net (code "4") (name "A+B") (class "Default")
      (node (ref "E11") (pin "2") (pinfunction "I1_2") (pintype "input"))
      (node (ref "E13") (pin "8") (pinfunction "O_8") (pintype "output"))
      (node (ref "E32") (pin "4") (pinfunction "I0_4") (pintype "input"))
    )
    (net (code "5") (name "BA") (class "Default")
      (node (ref "E3") (pin "8") (pinfunction "O_8") (pintype "output"))
      (node (ref "J2") (pin "JJ") (pinfunction "P_JJ") (pintype "passive"))
    )
    (net (code "6") (name "BB") (class "Default")
      (node (ref "E3") (pin "6") (pinfunction "O_6") (pintype "output"))
      (node (ref "J2") (pin "NN") (pinfunction "P_NN") (pintype "passive"))
    )
    (net (code "7") (name "BTP3") (class "Default")
      (node (ref "E11") (pin "9") (pinfunction "I0_9") (pintype "input"))
      (node (ref "E13") (pin "4") (pinfunction "I0_4") (pintype "input"))
      (node (ref "E22") (pin "10") (pinfunction "I1_10") (pintype "input"))
      (node (ref "E22") (pin "12") (pinfunction "I0_12") (pintype "input"))
      (node (ref "E22") (pin "2") (pinfunction "I1_2") (pintype "input"))
      (node (ref "E22") (pin "4") (pinfunction "I0_4") (pintype "input"))
      (node (ref "E26") (pin "8") (pinfunction "O_8") (pintype "output"))
    )
    (net (code "8") (name "CLOCK_PULSE") (class "Default")
      (node (ref "E2") (pin "11") (pinfunction "CLK_11") (pintype "input"))
      (node (ref "E32") (pin "9") (pinfunction "I0_9") (pintype "input"))
      (node (ref "E5") (pin "10") (pinfunction "I1_10") (pintype "input"))
      (node (ref "E8") (pin "10") (pinfunction "O_10") (pintype "output"))
    )
    (net (code "9") (name "COIL_BIAS") (class "Default")
      (node (ref "J1") (pin "BB") (pinfunction "P_BB") (pintype "passive"))
      (node (ref "R10") (pin "1") (pinfunction "1_1") (pintype "passive"))
    )
    (net (code "10") (name "ENABLE") (class "Default")
      (node (ref "E1") (pin "3") (pinfunction "I0_3") (pintype "input"))
      (node (ref "E26") (pin "3") (pinfunction "I_3") (pintype "input"))
      (node (ref "E4") (pin "1") (pinfunction "P$1_1") (pintype "input"))
      (node (ref "E4") (pin "2") (pinfunction "P$2_2") (pintype "input"))
      (node (ref "E5") (pin "11") (pinfunction "O_11") (pintype "output"))
      (node (ref "E7") (pin "1") (pinfunction "P$1_1") (pintype "input"))
      (node (ref "E7") (pin "2") (pinfunction "P$2_2") (pintype "input"))
      (node (ref "R20") (pin "1") (pinfunction "1_1") (pintype "passive"))
    )
    (net (code "11") (name "FEED_HOLE") (class "Default")
      (node (ref "J2") (pin "DD") (pinfunction "P_DD") (pintype "passive"))
      (node (ref "R1") (pin "1") (pinfunction "1_1") (pintype "passive"))
    )
    (net (code "12") (name "GND") (class "Default")
      (node (ref "C1") (pin "2") (pinfunction "2_2") (pintype "passive"))
      (node (ref "C10") (pin "2") (pinfunction "2_2") (pintype "passive"))
      (node (ref "C11") (pin "2") (pinfunction "2_2") (pintype "passive"))
      (node (ref "C12") (pin "2") (pinfunction "2_2") (pintype "passive"))
      (node (ref "C13") (pin "2") (pinfunction "2_2") (pintype "passive"))
      (node (ref "C14") (pin "2") (pinfunction "2_2") (pintype "passive"))
      (node (ref "C15") (pin "2") (pinfunction "2_2") (pintype "passive"))
      (node (ref "C16") (pin "2") (pinfunction "2_2") (pintype "passive"))
      (node (ref "C17") (pin "2") (pinfunction "2_2") (pintype "passive"))
      (node (ref "C18") (pin "2") (pinfunction "2_2") (pintype "passive"))
      (node (ref "C19") (pin "2") (pinfunction "2_2") (pintype "passive"))
      (node (ref "C2") (pin "2") (pinfunction "2_2") (pintype "passive"))
      (node (ref "C20") (pin "2") (pinfunction "2_2") (pintype "passive"))
      (node (ref "C21") (pin "2") (pinfunction "2_2") (pintype "passive"))
      (node (ref "C22") (pin "2") (pinfunction "2_2") (pintype "passive"))
      (node (ref "C23") (pin "2") (pinfunction "2_2") (pintype "passive"))
      (node (ref "C24") (pin "2") (pinfunction "2_2") (pintype "passive"))
      (node (ref "C25") (pin "2") (pinfunction "2_2") (pintype "passive"))
      (node (ref "C26") (pin "2") (pinfunction "2_2") (pintype "passive"))
      (node (ref "C27") (pin "2") (pinfunction "2_2") (pintype "passive"))
      (node (ref "C28") (pin "2") (pinfunction "2_2") (pintype "passive"))
      (node (ref "C29") (pin "2") (pinfunction "2_2") (pintype "passive"))
      (node (ref "C3") (pin "2") (pinfunction "2_2") (pintype "passive"))
      (node (ref "C30") (pin "2") (pinfunction "2_2") (pintype "passive"))
      (node (ref "C31") (pin "-") (pinfunction "-_-") (pintype "passive"))
      (node (ref "C32") (pin "2") (pinfunction "2_2") (pintype "passive"))
      (node (ref "C33") (pin "2") (pinfunction "2_2") (pintype "passive"))
      (node (ref "C34") (pin "2") (pinfunction "2_2") (pintype "passive"))
      (node (ref "C35") (pin "2") (pinfunction "2_2") (pintype "passive"))
      (node (ref "C36") (pin "2") (pinfunction "2_2") (pintype "passive"))
      (node (ref "C37") (pin "2") (pinfunction "2_2") (pintype "passive"))
      (node (ref "C38") (pin "2") (pinfunction "2_2") (pintype "passive"))
      (node (ref "C39") (pin "2") (pinfunction "2_2") (pintype "passive"))
      (node (ref "C4") (pin "2") (pinfunction "2_2") (pintype "passive"))
      (node (ref "C40") (pin "2") (pinfunction "2_2") (pintype "passive"))
      (node (ref "C41") (pin "2") (pinfunction "2_2") (pintype "passive"))
      (node (ref "C42") (pin "2") (pinfunction "2_2") (pintype "passive"))
      (node (ref "C43") (pin "2") (pinfunction "2_2") (pintype "passive"))
      (node (ref "C44") (pin "2") (pinfunction "2_2") (pintype "passive"))
      (node (ref "C45") (pin "-") (pinfunction "-_-") (pintype "passive"))
      (node (ref "C46") (pin "-") (pinfunction "-_-") (pintype "passive"))
      (node (ref "C47") (pin "-") (pinfunction "-_-") (pintype "passive"))
      (node (ref "C48") (pin "-") (pinfunction "-_-") (pintype "passive"))
      (node (ref "C5") (pin "2") (pinfunction "2_2") (pintype "passive"))
      (node (ref "C51") (pin "2") (pinfunction "2_2") (pintype "passive"))
      (node (ref "C55") (pin "2") (pinfunction "2_2") (pintype "passive"))
      (node (ref "C6") (pin "2") (pinfunction "2_2") (pintype "passive"))
      (node (ref "C60") (pin "2") (pinfunction "2_2") (pintype "passive"))
      (node (ref "C61") (pin "2") (pinfunction "2_2") (pintype "passive"))
      (node (ref "C62") (pin "2") (pinfunction "2_2") (pintype "passive"))
      (node (ref "C63") (pin "2") (pinfunction "2_2") (pintype "passive"))
      (node (ref "C64") (pin "2") (pinfunction "2_2") (pintype "passive"))
      (node (ref "C65") (pin "-") (pinfunction "-_-") (pintype "passive"))
      (node (ref "C66") (pin "+") (pinfunction "+_+") (pintype "passive"))
      (node (ref "C7") (pin "2") (pinfunction "2_2") (pintype "passive"))
      (node (ref "C8") (pin "2") (pinfunction "2_2") (pintype "passive"))
      (node (ref "C9") (pin "2") (pinfunction "2_2") (pintype "passive"))
      (node (ref "D4") (pin "A") (pinfunction "A_A") (pintype "passive"))
      (node (ref "D5") (pin "C") (pinfunction "C_C") (pintype "passive"))
      (node (ref "D7") (pin "A") (pinfunction "A_A") (pintype "passive"))
      (node (ref "E10") (pin "2") (pinfunction "D_2") (pintype "input"))
      (node (ref "E12") (pin "2") (pinfunction "D_2") (pintype "input"))
      (node (ref "E15") (pin "1") (pinfunction "P$1_1") (pintype "input"))
      (node (ref "E15") (pin "2") (pinfunction "P$2_2") (pintype "input"))
      (node (ref "E16") (pin "6") (pinfunction "I0_6") (pintype "input"))
      (node (ref "E2") (pin "2") (pinfunction "D_2") (pintype "input"))
      (node (ref "E24") (pin "11") (pinfunction "I0_11") (pintype "input"))
      (node (ref "E30") (pin "6") (pinfunction "I0_6") (pintype "input"))
      (node (ref "E34") (pin "13") (pinfunction "S_13") (pintype "input"))
      (node (ref "E34") (pin "4") (pinfunction "D_4") (pintype "input"))
      (node (ref "E37") (pin "13") (pinfunction "S_13") (pintype "input"))
      (node (ref "E37") (pin "4") (pinfunction "D_4") (pintype "input"))
      (node (ref "E40") (pin "13") (pinfunction "S_13") (pintype "input"))
      (node (ref "E40") (pin "4") (pinfunction "D_4") (pintype "input"))
      (node (ref "E43") (pin "13") (pinfunction "S_13") (pintype "input"))
      (node (ref "E43") (pin "4") (pinfunction "D_4") (pintype "input"))
      (node (ref "J1") (pin "A") (pinfunction "P_A") (pintype "passive"))
      (node (ref "J1") (pin "AA") (pinfunction "P_AA") (pintype "passive"))
      (node (ref "J1") (pin "B") (pinfunction "P_B") (pintype "passive"))
      (node (ref "J1") (pin "C") (pinfunction "P_C") (pintype "passive"))
      (node (ref "J1") (pin "CC") (pinfunction "P_CC") (pintype "passive"))
      (node (ref "J1") (pin "E") (pinfunction "P_E") (pintype "passive"))
      (node (ref "J1") (pin "EE") (pinfunction "P_EE") (pintype "passive"))
      (node (ref "J1") (pin "H") (pinfunction "P_H") (pintype "passive"))
      (node (ref "J1") (pin "HH") (pinfunction "P_HH") (pintype "passive"))
      (node (ref "J1") (pin "K") (pinfunction "P_K") (pintype "passive"))
      (node (ref "J1") (pin "KK") (pinfunction "P_KK") (pintype "passive"))
      (node (ref "J1") (pin "L") (pinfunction "P_L") (pintype "passive"))
      (node (ref "J1") (pin "M") (pinfunction "P_M") (pintype "passive"))
      (node (ref "J1") (pin "MM") (pinfunction "P_MM") (pintype "passive"))
      (node (ref "J1") (pin "NN") (pinfunction "P_NN") (pintype "passive"))
      (node (ref "J1") (pin "P") (pinfunction "P_P") (pintype "passive"))
      (node (ref "J1") (pin "PP") (pinfunction "P_PP") (pintype "passive"))
      (node (ref "J1") (pin "RR") (pinfunction "P_RR") (pintype "passive"))
      (node (ref "J1") (pin "S") (pinfunction "P_S") (pintype "passive"))
      (node (ref "J1") (pin "SS") (pinfunction "P_SS") (pintype "passive"))
      (node (ref "J1") (pin "TT") (pinfunction "P_TT") (pintype "passive"))
      (node (ref "J1") (pin "U") (pinfunction "P_U") (pintype "passive"))
      (node (ref "J1") (pin "UU") (pinfunction "P_UU") (pintype "passive"))
      (node (ref "J1") (pin "VV") (pinfunction "P_VV") (pintype "passive"))
      (node (ref "J1") (pin "W") (pinfunction "P_W") (pintype "passive"))
      (node (ref "J1") (pin "Y") (pinfunction "P_Y") (pintype "passive"))
      (node (ref "J2") (pin "A") (pinfunction "P_A") (pintype "passive"))
      (node (ref "J2") (pin "AA") (pinfunction "P_AA") (pintype "passive"))
      (node (ref "J2") (pin "B") (pinfunction "P_B") (pintype "passive"))
      (node (ref "J2") (pin "C") (pinfunction "P_C") (pintype "passive"))
      (node (ref "J2") (pin "CC") (pinfunction "P_CC") (pintype "passive"))
      (node (ref "J2") (pin "D") (pinfunction "P_D") (pintype "passive"))
      (node (ref "J2") (pin "E") (pinfunction "P_E") (pintype "passive"))
      (node (ref "J2") (pin "EE") (pinfunction "P_EE") (pintype "passive"))
      (node (ref "J2") (pin "H") (pinfunction "P_H") (pintype "passive"))
      (node (ref "J2") (pin "HH") (pinfunction "P_HH") (pintype "passive"))
      (node (ref "J2") (pin "J") (pinfunction "P_J") (pintype "passive"))
      (node (ref "J2") (pin "K") (pinfunction "P_K") (pintype "passive"))
      (node (ref "J2") (pin "KK") (pinfunction "P_KK") (pintype "passive"))
      (node (ref "J2") (pin "M") (pinfunction "P_M") (pintype "passive"))
      (node (ref "J2") (pin "MM") (pinfunction "P_MM") (pintype "passive"))
      (node (ref "J2") (pin "P") (pinfunction "P_P") (pintype "passive"))
      (node (ref "J2") (pin "PP") (pinfunction "P_PP") (pintype "passive"))
      (node (ref "J2") (pin "S") (pinfunction "P_S") (pintype "passive"))
      (node (ref "J2") (pin "SS") (pinfunction "P_SS") (pintype "passive"))
      (node (ref "J2") (pin "U") (pinfunction "P_U") (pintype "passive"))
      (node (ref "J2") (pin "UU") (pinfunction "P_UU") (pintype "passive"))
      (node (ref "J2") (pin "VV") (pinfunction "P_VV") (pintype "passive"))
      (node (ref "J2") (pin "W") (pinfunction "P_W") (pintype "passive"))
      (node (ref "J2") (pin "Y") (pinfunction "P_Y") (pintype "passive"))
      (node (ref "OMNIBUS") (pin "AC2") (pinfunction "1_AC2") (pintype "bidirectional"))
      (node (ref "OMNIBUS") (pin "AF1") (pinfunction "1_AF1") (pintype "bidirectional"))
      (node (ref "OMNIBUS") (pin "AF2") (pinfunction "1_AF2") (pintype "bidirectional"))
      (node (ref "OMNIBUS") (pin "AN1") (pinfunction "1_AN1") (pintype "bidirectional"))
      (node (ref "OMNIBUS") (pin "AN2") (pinfunction "1_AN2") (pintype "bidirectional"))
      (node (ref "OMNIBUS") (pin "AT1") (pinfunction "1_AT1") (pintype "bidirectional"))
      (node (ref "OMNIBUS") (pin "AT2") (pinfunction "1_AT2") (pintype "bidirectional"))
      (node (ref "OMNIBUS") (pin "BC1") (pinfunction "1_BC1") (pintype "bidirectional"))
      (node (ref "OMNIBUS") (pin "BC2") (pinfunction "1_BC2") (pintype "bidirectional"))
      (node (ref "OMNIBUS") (pin "BF1") (pinfunction "1_BF1") (pintype "bidirectional"))
      (node (ref "OMNIBUS") (pin "BF2") (pinfunction "1_BF2") (pintype "bidirectional"))
      (node (ref "OMNIBUS") (pin "BN1") (pinfunction "1_BN1") (pintype "bidirectional"))
      (node (ref "OMNIBUS") (pin "BN2") (pinfunction "1_BN2") (pintype "bidirectional"))
      (node (ref "OMNIBUS") (pin "BT1") (pinfunction "1_BT1") (pintype "bidirectional"))
      (node (ref "OMNIBUS") (pin "BT2") (pinfunction "1_BT2") (pintype "bidirectional"))
      (node (ref "OMNIBUS") (pin "CC1") (pinfunction "1_CC1") (pintype "bidirectional"))
      (node (ref "OMNIBUS") (pin "CC2") (pinfunction "1_CC2") (pintype "bidirectional"))
      (node (ref "OMNIBUS") (pin "CF1") (pinfunction "1_CF1") (pintype "bidirectional"))
      (node (ref "OMNIBUS") (pin "CF2") (pinfunction "1_CF2") (pintype "bidirectional"))
      (node (ref "OMNIBUS") (pin "CN1") (pinfunction "1_CN1") (pintype "bidirectional"))
      (node (ref "OMNIBUS") (pin "CN2") (pinfunction "1_CN2") (pintype "bidirectional"))
      (node (ref "OMNIBUS") (pin "CT1") (pinfunction "1_CT1") (pintype "bidirectional"))
      (node (ref "OMNIBUS") (pin "CT2") (pinfunction "1_CT2") (pintype "bidirectional"))
      (node (ref "OMNIBUS") (pin "DC1") (pinfunction "1_DC1") (pintype "bidirectional"))
      (node (ref "OMNIBUS") (pin "DC2") (pinfunction "1_DC2") (pintype "bidirectional"))
      (node (ref "OMNIBUS") (pin "DF1") (pinfunction "1_DF1") (pintype "bidirectional"))
      (node (ref "OMNIBUS") (pin "DF2") (pinfunction "1_DF2") (pintype "bidirectional"))
      (node (ref "OMNIBUS") (pin "DN1") (pinfunction "1_DN1") (pintype "bidirectional"))
      (node (ref "OMNIBUS") (pin "DN2") (pinfunction "1_DN2") (pintype "bidirectional"))
      (node (ref "OMNIBUS") (pin "DT1") (pinfunction "1_DT1") (pintype "bidirectional"))
      (node (ref "OMNIBUS") (pin "DT2") (pinfunction "1_DT2") (pintype "bidirectional"))
      (node (ref "R12") (pin "1") (pinfunction "1_1") (pintype "passive"))
      (node (ref "R13") (pin "1") (pinfunction "1_1") (pintype "passive"))
      (node (ref "R27") (pin "3") (pinfunction "E_3") (pintype "passive"))
      (node (ref "R36") (pin "1") (pinfunction "1_1") (pintype "passive"))
      (node (ref "R46") (pin "1") (pinfunction "1_1") (pintype "passive"))
      (node (ref "R5") (pin "1") (pinfunction "1_1") (pintype "passive"))
      (node (ref "R6") (pin "1") (pinfunction "1_1") (pintype "passive"))
    )
    (net (code "13") (name "HAVE_TAPE") (class "Default")
      (node (ref "E11") (pin "10") (pinfunction "I1_10") (pintype "input"))
      (node (ref "E26") (pin "10") (pinfunction "O_10") (pintype "output"))
    )
    (net (code "14") (name "INITIALIZE") (class "Default")
      (node (ref "E30") (pin "7") (pinfunction "I1_7") (pintype "input"))
      (node (ref "OMNIBUS") (pin "CR1") (pinfunction "1_CR1") (pintype "bidirectional"))
    )
    (net (code "15") (name "INT_ENA") (class "Default")
      (node (ref "E14") (pin "5") (pinfunction "Q_5") (pintype "output"))
      (node (ref "E18") (pin "11") (pinfunction "I0_11") (pintype "input"))
      (node (ref "E18") (pin "9") (pinfunction "I1_9") (pintype "input"))
    )
    (net (code "16") (name "IOT01") (class "Default")
      (node (ref "E17") (pin "5") (pinfunction "I0_5") (pintype "input"))
      (node (ref "E17") (pin "6") (pinfunction "I1_6") (pintype "input"))
      (node (ref "E21") (pin "3") (pinfunction "O_3") (pintype "output"))
      (node (ref "E24") (pin "4") (pinfunction "I0_4") (pintype "input"))
      (node (ref "E29") (pin "13") (pinfunction "I_13") (pintype "input"))
    )
    (net (code "17") (name "IOT02") (class "Default")
      (node (ref "E17") (pin "2") (pinfunction "I0_2") (pintype "input"))
      (node (ref "E17") (pin "3") (pinfunction "I1_3") (pintype "input"))
      (node (ref "E24") (pin "5") (pinfunction "I1_5") (pintype "input"))
      (node (ref "E25") (pin "3") (pinfunction "O_3") (pintype "output"))
      (node (ref "E29") (pin "5") (pinfunction "I_5") (pintype "input"))
    )
    (net (code "18") (name "MOTOR_POWER") (class "Default")
      (node (ref "E8") (pin "2") (pinfunction "O_2") (pintype "output"))
      (node (ref "J2") (pin "RR") (pinfunction "P_RR") (pintype "passive"))
    )
    (net (code "19") (name "Net-(C31-Pad+)") (class "Default")
      (node (ref "C31") (pin "+") (pinfunction "+_+") (pintype "passive"))
      (node (ref "C48") (pin "+") (pinfunction "+_+") (pintype "passive"))
      (node (ref "R1") (pin "2") (pinfunction "2_2") (pintype "passive"))
      (node (ref "R2") (pin "1") (pinfunction "1_1") (pintype "passive"))
    )
    (net (code "20") (name "Net-(C59-Pad-)") (class "Default")
      (node (ref "C59") (pin "-") (pinfunction "-_-") (pintype "passive"))
      (node (ref "R44") (pin "1") (pinfunction "1_1") (pintype "passive"))
    )
    (net (code "21") (name "Net-(D1-PadC)") (class "Default")
      (node (ref "D1") (pin "C") (pinfunction "C_C") (pintype "passive"))
      (node (ref "D2") (pin "A") (pinfunction "A_A") (pintype "passive"))
    )
    (net (code "22") (name "Net-(D2-PadC)") (class "Default")
      (node (ref "D2") (pin "C") (pinfunction "C_C") (pintype "passive"))
      (node (ref "D3") (pin "A") (pinfunction "A_A") (pintype "passive"))
    )
    (net (code "23") (name "Net-(D3-PadC)") (class "Default")
      (node (ref "D3") (pin "C") (pinfunction "C_C") (pintype "passive"))
      (node (ref "D5") (pin "A") (pinfunction "A_A") (pintype "passive"))
    )
    (net (code "24") (name "Net-(E1A-O)") (class "Default")
      (node (ref "E1") (pin "12") (pinfunction "O_12") (pintype "output"))
      (node (ref "E8") (pin "3") (pinfunction "I_3") (pintype "input"))
    )
    (net (code "25") (name "Net-(E1B-I1)") (class "Default")
      (node (ref "C62") (pin "1") (pinfunction "1_1") (pintype "passive"))
      (node (ref "E1") (pin "4") (pinfunction "I1_4") (pintype "input"))
      (node (ref "R38") (pin "2") (pinfunction "2_2") (pintype "passive"))
    )
    (net (code "26") (name "Net-(E1B-I2)") (class "Default")
      (node (ref "E1") (pin "5") (pinfunction "I2_5") (pintype "input"))
      (node (ref "E1") (pin "8") (pinfunction "O_8") (pintype "output"))
      (node (ref "E8") (pin "9") (pinfunction "I_9") (pintype "input"))
    )
    (net (code "27") (name "Net-(E1C-I0)") (class "Default")
      (node (ref "E1") (pin "10") (pinfunction "I1_10") (pintype "input"))
      (node (ref "E1") (pin "9") (pinfunction "I0_9") (pintype "input"))
      (node (ref "E3") (pin "10") (pinfunction "O_10") (pintype "output"))
      (node (ref "E5") (pin "1") (pinfunction "I0_1") (pintype "input"))
    )
    (net (code "28") (name "Net-(E1C-I2)") (class "Default")
      (node (ref "C61") (pin "1") (pinfunction "1_1") (pintype "passive"))
      (node (ref "E1") (pin "11") (pinfunction "I2_11") (pintype "input"))
      (node (ref "R35") (pin "2") (pinfunction "2_2") (pintype "passive"))
    )
    (net (code "29") (name "Net-(E2B-PRE)") (class "Default")
      (node (ref "E2") (pin "10") (pinfunction "PRE_10") (pintype "input"))
      (node (ref "E8") (pin "12") (pinfunction "O_12") (pintype "output"))
    )
    (net (code "30") (name "Net-(E2B-~{Q})") (class "Default")
      (node (ref "E2") (pin "8") (pinfunction "~{Q}_8") (pintype "output"))
      (node (ref "E35") (pin "1") (pinfunction "I0_1") (pintype "input"))
      (node (ref "E35") (pin "2") (pinfunction "I1_2") (pintype "input"))
      (node (ref "E5") (pin "12") (pinfunction "I0_12") (pintype "input"))
    )
    (net (code "31") (name "Net-(E3A-I)") (class "Default")
      (node (ref "E3") (pin "1") (pinfunction "I_1") (pintype "input"))
      (node (ref "E6") (pin "10") (pinfunction "I1_10") (pintype "input"))
      (node (ref "E9") (pin "9") (pinfunction "Q_9") (pintype "output"))
    )
    (net (code "32") (name "Net-(E3B-I)") (class "Default")
      (node (ref "E3") (pin "3") (pinfunction "I_3") (pintype "input"))
      (node (ref "E6") (pin "9") (pinfunction "I0_9") (pintype "input"))
      (node (ref "E9") (pin "12") (pinfunction "D_12") (pintype "input"))
      (node (ref "E9") (pin "5") (pinfunction "Q_5") (pintype "output"))
    )
    (net (code "33") (name "Net-(E4A-P$3)") (class "Default")
      (node (ref "E4") (pin "3") (pinfunction "P$3_3") (pintype "input"))
      (node (ref "E4") (pin "4") (pinfunction "P$4_4") (pintype "input"))
      (node (ref "E7") (pin "3") (pinfunction "P$3_3") (pintype "input"))
      (node (ref "E7") (pin "4") (pinfunction "P$4_4") (pintype "input"))
      (node (ref "R15") (pin "1") (pinfunction "1_1") (pintype "passive"))
    )
    (net (code "34") (name "Net-(E4A-P$5)") (class "Default")
      (node (ref "C52") (pin "-") (pinfunction "-_-") (pintype "passive"))
      (node (ref "E4") (pin "11") (pinfunction "P$5_11") (pintype "bidirectional"))
    )
    (net (code "35") (name "Net-(E4A-P$6)") (class "Default")
      (node (ref "C52") (pin "+") (pinfunction "+_+") (pintype "passive"))
      (node (ref "E4") (pin "13") (pinfunction "P$6_13") (pintype "bidirectional"))
      (node (ref "R16") (pin "1") (pinfunction "1_1") (pintype "passive"))
    )
    (net (code "36") (name "Net-(E5A-I1)") (class "Default")
      (node (ref "C60") (pin "1") (pinfunction "1_1") (pintype "passive"))
      (node (ref "E5") (pin "2") (pinfunction "I1_2") (pintype "input"))
      (node (ref "R34") (pin "2") (pinfunction "2_2") (pintype "passive"))
    )
    (net (code "37") (name "Net-(E5B-I0)") (class "Default")
      (node (ref "E5") (pin "4") (pinfunction "I0_4") (pintype "input"))
      (node (ref "E5") (pin "8") (pinfunction "O_8") (pintype "output"))
    )
    (net (code "38") (name "Net-(E5B-O)") (class "Default")
      (node (ref "E5") (pin "6") (pinfunction "O_6") (pintype "output"))
      (node (ref "E8") (pin "5") (pinfunction "I_5") (pintype "input"))
    )
    (net (code "39") (name "Net-(E6A-O)") (class "Default")
      (node (ref "E6") (pin "3") (pinfunction "O_3") (pintype "output"))
      (node (ref "E8") (pin "13") (pinfunction "I_13") (pintype "input"))
    )
    (net (code "40") (name "Net-(E6D-I0)") (class "Default")
      (node (ref "C32") (pin "1") (pinfunction "1_1") (pintype "passive"))
      (node (ref "E6") (pin "12") (pinfunction "I0_12") (pintype "input"))
      (node (ref "R18") (pin "2") (pinfunction "2_2") (pintype "passive"))
    )
    (net (code "41") (name "Net-(E6D-I1)") (class "Default")
      (node (ref "E6") (pin "13") (pinfunction "I1_13") (pintype "input"))
      (node (ref "E7") (pin "6") (pinfunction "~{Q}_6") (pintype "output"))
    )
    (net (code "42") (name "Net-(E7A-P$5)") (class "Default")
      (node (ref "C53") (pin "-") (pinfunction "-_-") (pintype "passive"))
      (node (ref "E7") (pin "11") (pinfunction "P$5_11") (pintype "bidirectional"))
    )
    (net (code "43") (name "Net-(E7A-P$6)") (class "Default")
      (node (ref "C53") (pin "+") (pinfunction "+_+") (pintype "passive"))
      (node (ref "E7") (pin "13") (pinfunction "P$6_13") (pintype "bidirectional"))
      (node (ref "R17") (pin "1") (pinfunction "1_1") (pintype "passive"))
    )
    (net (code "44") (name "Net-(E7A-Q)") (class "Default")
      (node (ref "E7") (pin "8") (pinfunction "Q_8") (pintype "output"))
      (node (ref "R18") (pin "1") (pinfunction "1_1") (pintype "passive"))
    )
    (net (code "45") (name "Net-(E8D-O)") (class "Default")
      (node (ref "E8") (pin "8") (pinfunction "O_8") (pintype "output"))
      (node (ref "R38") (pin "1") (pinfunction "1_1") (pintype "passive"))
    )
    (net (code "46") (name "Net-(E9A-CLR)") (class "Default")
      (node (ref "E9") (pin "1") (pinfunction "CLR_1") (pintype "input"))
      (node (ref "E9") (pin "10") (pinfunction "PRE_10") (pintype "input"))
      (node (ref "E9") (pin "13") (pinfunction "CLR_13") (pintype "input"))
      (node (ref "E9") (pin "4") (pinfunction "PRE_4") (pintype "input"))
      (node (ref "R41") (pin "1") (pinfunction "1_1") (pintype "passive"))
    )
    (net (code "47") (name "Net-(E10A-~{Q})") (class "Default")
      (node (ref "E10") (pin "11") (pinfunction "CLK_11") (pintype "input"))
      (node (ref "E10") (pin "6") (pinfunction "~{Q}_6") (pintype "output"))
      (node (ref "E13") (pin "2") (pinfunction "I1_2") (pintype "input"))
    )
    (net (code "48") (name "Net-(E10B-CLR)") (class "Default")
      (node (ref "E10") (pin "13") (pinfunction "CLR_13") (pintype "input"))
      (node (ref "E44") (pin "2") (pinfunction "O_2") (pintype "output"))
    )
    (net (code "49") (name "Net-(E10B-D)") (class "Default")
      (node (ref "E10") (pin "10") (pinfunction "PRE_10") (pintype "input"))
      (node (ref "E10") (pin "12") (pinfunction "D_12") (pintype "input"))
      (node (ref "E14") (pin "2") (pinfunction "D_2") (pintype "input"))
      (node (ref "R14") (pin "1") (pinfunction "1_1") (pintype "passive"))
    )
    (net (code "50") (name "Net-(E11A-O)") (class "Default")
      (node (ref "E11") (pin "12") (pinfunction "O_12") (pintype "output"))
      (node (ref "E2") (pin "12") (pinfunction "D_12") (pintype "input"))
    )
    (net (code "51") (name "Net-(E11B-O)") (class "Default")
      (node (ref "E11") (pin "6") (pinfunction "O_6") (pintype "output"))
      (node (ref "E6") (pin "2") (pinfunction "I1_2") (pintype "input"))
    )
    (net (code "52") (name "Net-(E11C-I2)") (class "Default")
      (node (ref "E11") (pin "11") (pinfunction "I2_11") (pintype "input"))
      (node (ref "E28") (pin "6") (pinfunction "O_6") (pintype "output"))
    )
    (net (code "53") (name "Net-(E12A-~{Q})") (class "Default")
      (node (ref "E12") (pin "6") (pinfunction "~{Q}_6") (pintype "output"))
      (node (ref "E8") (pin "1") (pinfunction "I_1") (pintype "input"))
    )
    (net (code "54") (name "Net-(E12B-CLR)") (class "Default")
      (node (ref "E12") (pin "13") (pinfunction "CLR_13") (pintype "input"))
      (node (ref "E8") (pin "4") (pinfunction "O_4") (pintype "output"))
    )
    (net (code "55") (name "Net-(E12B-PRE)") (class "Default")
      (node (ref "E12") (pin "10") (pinfunction "PRE_10") (pintype "input"))
      (node (ref "R42") (pin "1") (pinfunction "1_1") (pintype "passive"))
    )
    (net (code "56") (name "Net-(E12B-Q)") (class "Default")
      (node (ref "E12") (pin "9") (pinfunction "Q_9") (pintype "output"))
      (node (ref "E18") (pin "5") (pinfunction "I0_5") (pintype "input"))
      (node (ref "E18") (pin "8") (pinfunction "I0_8") (pintype "input"))
    )
    (net (code "57") (name "Net-(E13A-O)") (class "Default")
      (node (ref "E13") (pin "12") (pinfunction "I0_12") (pintype "input"))
      (node (ref "E13") (pin "3") (pinfunction "O_3") (pintype "output"))
    )
    (net (code "58") (name "Net-(E13B-O)") (class "Default")
      (node (ref "E13") (pin "6") (pinfunction "O_6") (pintype "output"))
      (node (ref "E35") (pin "12") (pinfunction "I2_12") (pintype "input"))
      (node (ref "E35") (pin "13") (pinfunction "I3_13") (pintype "input"))
    )
    (net (code "59") (name "Net-(E13C-I0)") (class "Default")
      (node (ref "E13") (pin "9") (pinfunction "I0_9") (pintype "input"))
      (node (ref "E3") (pin "9") (pinfunction "I_9") (pintype "input"))
      (node (ref "E9") (pin "6") (pinfunction "~{Q}_6") (pintype "output"))
    )
    (net (code "60") (name "Net-(E13C-I1)") (class "Default")
      (node (ref "E13") (pin "10") (pinfunction "I1_10") (pintype "input"))
      (node (ref "E3") (pin "5") (pinfunction "I_5") (pintype "input"))
      (node (ref "E9") (pin "2") (pinfunction "D_2") (pintype "input"))
      (node (ref "E9") (pin "8") (pinfunction "~{Q}_8") (pintype "output"))
    )
    (net (code "61") (name "Net-(E13D-O)") (class "Default")
      (node (ref "E13") (pin "11") (pinfunction "O_11") (pintype "output"))
      (node (ref "E14") (pin "12") (pinfunction "D_12") (pintype "input"))
    )
    (net (code "62") (name "Net-(E14A-CLK)") (class "Default")
      (node (ref "E14") (pin "3") (pinfunction "CLK_3") (pintype "input"))
      (node (ref "E22") (pin "8") (pinfunction "O_8") (pintype "output"))
    )
    (net (code "63") (name "Net-(E14A-CLR)") (class "Default")
      (node (ref "E14") (pin "1") (pinfunction "CLR_1") (pintype "input"))
      (node (ref "E22") (pin "6") (pinfunction "O_6") (pintype "output"))
    )
    (net (code "64") (name "Net-(E14B-CLK)") (class "Default")
      (node (ref "E14") (pin "11") (pinfunction "CLK_11") (pintype "input"))
      (node (ref "Q10") (pin "3") (pinfunction "C_3") (pintype "passive"))
      (node (ref "R13") (pin "2") (pinfunction "2_2") (pintype "passive"))
    )
    (net (code "65") (name "Net-(E14B-~{Q})") (class "Default")
      (node (ref "E14") (pin "8") (pinfunction "~{Q}_8") (pintype "output"))
      (node (ref "E15") (pin "3") (pinfunction "P$3_3") (pintype "input"))
      (node (ref "E15") (pin "4") (pinfunction "P$4_4") (pintype "input"))
    )
    (net (code "66") (name "Net-(E15A-P$5)") (class "Default")
      (node (ref "C56") (pin "-") (pinfunction "-_-") (pintype "passive"))
      (node (ref "E15") (pin "11") (pinfunction "P$5_11") (pintype "bidirectional"))
    )
    (net (code "67") (name "Net-(E15A-P$6)") (class "Default")
      (node (ref "C56") (pin "+") (pinfunction "+_+") (pintype "passive"))
      (node (ref "E15") (pin "13") (pinfunction "P$6_13") (pintype "bidirectional"))
      (node (ref "R47") (pin "1") (pinfunction "1_1") (pintype "passive"))
      (node (ref "R48") (pin "1") (pinfunction "1_1") (pintype "passive"))
    )
    (net (code "68") (name "Net-(E16B-O)") (class "Default")
      (node (ref "E16") (pin "2") (pinfunction "O_2") (pintype "output"))
      (node (ref "E20") (pin "10") (pinfunction "I1_10") (pintype "input"))
      (node (ref "E20") (pin "11") (pinfunction "I0_11") (pintype "input"))
      (node (ref "E20") (pin "5") (pinfunction "I1_5") (pintype "input"))
      (node (ref "E20") (pin "6") (pinfunction "I0_6") (pintype "input"))
      (node (ref "E21") (pin "12") (pinfunction "I6_12") (pintype "input"))
      (node (ref "E24") (pin "10") (pinfunction "I1_10") (pintype "input"))
      (node (ref "E24") (pin "6") (pinfunction "I0_6") (pintype "input"))
      (node (ref "E25") (pin "12") (pinfunction "I6_12") (pintype "input"))
    )
    (net (code "69") (name "Net-(E16D-I0)") (class "Default")
      (node (ref "E16") (pin "11") (pinfunction "I0_11") (pintype "input"))
      (node (ref "E16") (pin "12") (pinfunction "I1_12") (pintype "input"))
      (node (ref "E27") (pin "2") (pinfunction "D_2") (pintype "input"))
      (node (ref "E29") (pin "6") (pinfunction "O_6") (pintype "output"))
      (node (ref "R28") (pin "1") (pinfunction "1_1") (pintype "passive"))
    )
    (net (code "70") (name "Net-(E17D-I0)") (class "Default")
      (node (ref "E17") (pin "11") (pinfunction "I0_11") (pintype "input"))
      (node (ref "E3") (pin "12") (pinfunction "O_12") (pintype "output"))
    )
    (net (code "71") (name "Net-(E17D-I1)") (class "Default")
      (node (ref "E17") (pin "12") (pinfunction "I1_12") (pintype "input"))
      (node (ref "E19") (pin "8") (pinfunction "Q_8") (pintype "output"))
      (node (ref "E23") (pin "9") (pinfunction "I0_9") (pintype "input"))
    )
    (net (code "72") (name "Net-(E17D-O)") (class "Default")
      (node (ref "C54") (pin "-") (pinfunction "-_-") (pintype "passive"))
      (node (ref "E17") (pin "13") (pinfunction "O_13") (pintype "open_collector"))
      (node (ref "E19") (pin "11") (pinfunction "P$5_11") (pintype "bidirectional"))
    )
    (net (code "73") (name "Net-(E19A-P$1)") (class "Default")
      (node (ref "E19") (pin "1") (pinfunction "P$1_1") (pintype "input"))
      (node (ref "E19") (pin "2") (pinfunction "P$2_2") (pintype "input"))
      (node (ref "E23") (pin "1") (pinfunction "I0_1") (pintype "input"))
      (node (ref "E23") (pin "13") (pinfunction "I1_13") (pintype "input"))
      (node (ref "E26") (pin "2") (pinfunction "O_2") (pintype "output"))
    )
    (net (code "74") (name "Net-(E19A-P$3)") (class "Default")
      (node (ref "E19") (pin "3") (pinfunction "P$3_3") (pintype "input"))
      (node (ref "E19") (pin "4") (pinfunction "P$4_4") (pintype "input"))
      (node (ref "R52") (pin "1") (pinfunction "1_1") (pintype "passive"))
    )
    (net (code "75") (name "Net-(E19A-P$6)") (class "Default")
      (node (ref "C54") (pin "+") (pinfunction "+_+") (pintype "passive"))
      (node (ref "E19") (pin "13") (pinfunction "P$6_13") (pintype "bidirectional"))
      (node (ref "R30") (pin "1") (pinfunction "1_1") (pintype "passive"))
    )
    (net (code "76") (name "Net-(E20A-O)") (class "Default")
      (node (ref "E20") (pin "3") (pinfunction "O_3") (pintype "output"))
      (node (ref "E21") (pin "5") (pinfunction "I1_5") (pintype "input"))
    )
    (net (code "77") (name "Net-(E20B-O)") (class "Default")
      (node (ref "E20") (pin "2") (pinfunction "O_2") (pintype "output"))
      (node (ref "E21") (pin "6") (pinfunction "I2_6") (pintype "input"))
      (node (ref "E25") (pin "9") (pinfunction "I3_9") (pintype "input"))
    )
    (net (code "78") (name "Net-(E20C-O)") (class "Default")
      (node (ref "E20") (pin "14") (pinfunction "O_14") (pintype "output"))
      (node (ref "E21") (pin "9") (pinfunction "I3_9") (pintype "input"))
      (node (ref "E25") (pin "5") (pinfunction "I1_5") (pintype "input"))
    )
    (net (code "79") (name "Net-(E20D-O)") (class "Default")
      (node (ref "E20") (pin "13") (pinfunction "O_13") (pintype "output"))
      (node (ref "E21") (pin "10") (pinfunction "I4_10") (pintype "input"))
      (node (ref "E25") (pin "4") (pinfunction "I0_4") (pintype "input"))
    )
    (net (code "80") (name "Net-(E21E-I0)") (class "Default")
      (node (ref "E21") (pin "4") (pinfunction "I0_4") (pintype "input"))
      (node (ref "E24") (pin "14") (pinfunction "O_14") (pintype "output"))
      (node (ref "E25") (pin "11") (pinfunction "I5_11") (pintype "input"))
    )
    (net (code "81") (name "Net-(E23A-I1)") (class "Default")
      (node (ref "E23") (pin "2") (pinfunction "I1_2") (pintype "input"))
      (node (ref "E3") (pin "13") (pinfunction "I_13") (pintype "input"))
      (node (ref "E35") (pin "6") (pinfunction "O_6") (pintype "output"))
    )
    (net (code "82") (name "Net-(E23A-O)") (class "Default")
      (node (ref "E23") (pin "3") (pinfunction "O_3") (pintype "output"))
      (node (ref "E35") (pin "4") (pinfunction "I2_4") (pintype "input"))
      (node (ref "E35") (pin "5") (pinfunction "I3_5") (pintype "input"))
    )
    (net (code "83") (name "Net-(E23D-I0)") (class "Default")
      (node (ref "C22") (pin "1") (pinfunction "1_1") (pintype "passive"))
      (node (ref "E23") (pin "12") (pinfunction "I0_12") (pintype "input"))
      (node (ref "R51") (pin "2") (pinfunction "2_2") (pintype "passive"))
    )
    (net (code "84") (name "Net-(E23D-O)") (class "Default")
      (node (ref "E23") (pin "11") (pinfunction "O_11") (pintype "output"))
      (node (ref "R29") (pin "1") (pinfunction "1_1") (pintype "passive"))
    )
    (net (code "85") (name "Net-(E24A-O)") (class "Default")
      (node (ref "E24") (pin "3") (pinfunction "O_3") (pintype "output"))
      (node (ref "E30") (pin "10") (pinfunction "I1_10") (pintype "input"))
      (node (ref "E30") (pin "11") (pinfunction "I0_11") (pintype "input"))
      (node (ref "E30") (pin "5") (pinfunction "I1_5") (pintype "input"))
    )
    (net (code "86") (name "Net-(E24B-O)") (class "Default")
      (node (ref "E24") (pin "2") (pinfunction "O_2") (pintype "output"))
      (node (ref "E25") (pin "6") (pinfunction "I2_6") (pintype "input"))
    )
    (net (code "87") (name "Net-(E24D-O)") (class "Default")
      (node (ref "E24") (pin "13") (pinfunction "O_13") (pintype "output"))
      (node (ref "E26") (pin "9") (pinfunction "I_9") (pintype "input"))
    )
    (net (code "88") (name "Net-(E26A-I)") (class "Default")
      (node (ref "E26") (pin "1") (pinfunction "I_1") (pintype "input"))
      (node (ref "Q7") (pin "3") (pinfunction "C_3") (pintype "passive"))
      (node (ref "Q8") (pin "2") (pinfunction "B_2") (pintype "passive"))
      (node (ref "R3") (pin "1") (pinfunction "1_1") (pintype "passive"))
    )
    (net (code "89") (name "Net-(E26C-O)") (class "Default")
      (node (ref "E26") (pin "6") (pinfunction "O_6") (pintype "output"))
      (node (ref "E34") (pin "6") (pinfunction "C_6") (pintype "input"))
      (node (ref "E40") (pin "6") (pinfunction "C_6") (pintype "input"))
    )
    (net (code "90") (name "Net-(E27A-A)") (class "Default")
      (node (ref "E27") (pin "15") (pinfunction "A_15") (pintype "input"))
      (node (ref "E30") (pin "3") (pinfunction "O_3") (pintype "output"))
      (node (ref "E31") (pin "15") (pinfunction "A_15") (pintype "input"))
    )
    (net (code "91") (name "Net-(E27A-B)") (class "Default")
      (node (ref "E27") (pin "14") (pinfunction "B_14") (pintype "input"))
      (node (ref "E30") (pin "14") (pinfunction "O_14") (pintype "output"))
      (node (ref "E31") (pin "14") (pinfunction "B_14") (pintype "input"))
    )
    (net (code "92") (name "Net-(E27A-C)") (class "Default")
      (node (ref "E27") (pin "1") (pinfunction "C_1") (pintype "input"))
      (node (ref "E30") (pin "13") (pinfunction "O_13") (pintype "output"))
      (node (ref "E31") (pin "1") (pinfunction "C_1") (pintype "input"))
    )
    (net (code "93") (name "Net-(E29F-O)") (class "Default")
      (node (ref "E29") (pin "12") (pinfunction "O_12") (pintype "output"))
      (node (ref "E31") (pin "2") (pinfunction "D_2") (pintype "input"))
    )
    (net (code "94") (name "Net-(E32A-I0)") (class "Default")
      (node (ref "E32") (pin "1") (pinfunction "I0_1") (pintype "input"))
      (node (ref "E32") (pin "11") (pinfunction "O_11") (pintype "output"))
      (node (ref "R51") (pin "1") (pinfunction "1_1") (pintype "passive"))
    )
    (net (code "95") (name "Net-(E32A-I1)") (class "Default")
      (node (ref "C55") (pin "1") (pinfunction "1_1") (pintype "passive"))
      (node (ref "E32") (pin "2") (pinfunction "I1_2") (pintype "input"))
      (node (ref "E44") (pin "3") (pinfunction "I_3") (pintype "input"))
      (node (ref "R29") (pin "2") (pinfunction "2_2") (pintype "passive"))
    )
    (net (code "96") (name "Net-(E32A-O)") (class "Default")
      (node (ref "E32") (pin "13") (pinfunction "I1_13") (pintype "input"))
      (node (ref "E32") (pin "3") (pinfunction "O_3") (pintype "output"))
    )
    (net (code "97") (name "Net-(E32B-O)") (class "Default")
      (node (ref "E32") (pin "10") (pinfunction "I1_10") (pintype "input"))
      (node (ref "E32") (pin "6") (pinfunction "O_6") (pintype "output"))
    )
    (net (code "98") (name "Net-(E32C-O)") (class "Default")
      (node (ref "E32") (pin "12") (pinfunction "I0_12") (pintype "input"))
      (node (ref "E32") (pin "8") (pinfunction "O_8") (pintype "output"))
    )
    (net (code "99") (name "Net-(E33A-I0)") (class "Default")
      (node (ref "E33") (pin "2") (pinfunction "I0_2") (pintype "input"))
      (node (ref "E34") (pin "5") (pinfunction "Q0_5") (pintype "output"))
    )
    (net (code "100") (name "Net-(E33B-I0)") (class "Default")
      (node (ref "E33") (pin "5") (pinfunction "I0_5") (pintype "input"))
      (node (ref "E34") (pin "7") (pinfunction "Q1_7") (pintype "output"))
    )
    (net (code "101") (name "Net-(E33C-I1)") (class "Default")
      (node (ref "E33") (pin "9") (pinfunction "I1_9") (pintype "input"))
      (node (ref "E34") (pin "11") (pinfunction "Q3_11") (pintype "output"))
    )
    (net (code "102") (name "Net-(E33D-I1)") (class "Default")
      (node (ref "E33") (pin "12") (pinfunction "I1_12") (pintype "input"))
      (node (ref "E34") (pin "9") (pinfunction "Q2_9") (pintype "output"))
    )
    (net (code "103") (name "Net-(E34A-L)") (class "Default")
      (node (ref "E34") (pin "1") (pinfunction "R_1") (pintype "input"))
      (node (ref "E34") (pin "10") (pinfunction "L_10") (pintype "input"))
      (node (ref "E37") (pin "10") (pinfunction "L_10") (pintype "input"))
      (node (ref "E40") (pin "1") (pinfunction "R_1") (pintype "input"))
      (node (ref "E40") (pin "10") (pinfunction "L_10") (pintype "input"))
      (node (ref "E43") (pin "10") (pinfunction "L_10") (pintype "input"))
      (node (ref "R43") (pin "1") (pinfunction "1_1") (pintype "passive"))
    )
    (net (code "104") (name "Net-(E35D-O)") (class "Default")
      (node (ref "E35") (pin "8") (pinfunction "O_8") (pintype "output"))
      (node (ref "E44") (pin "1") (pinfunction "I_1") (pintype "input"))
    )
    (net (code "105") (name "Net-(E36A-O)") (class "Default")
      (node (ref "E36") (pin "3") (pinfunction "O_3") (pintype "output"))
      (node (ref "E37") (pin "3") (pinfunction "I0_3") (pintype "input"))
    )
    (net (code "106") (name "Net-(E36B-O)") (class "Default")
      (node (ref "E36") (pin "2") (pinfunction "O_2") (pintype "output"))
      (node (ref "E37") (pin "2") (pinfunction "I1_2") (pintype "input"))
    )
    (net (code "107") (name "Net-(E36C-O)") (class "Default")
      (node (ref "E36") (pin "14") (pinfunction "O_14") (pintype "output"))
      (node (ref "E37") (pin "14") (pinfunction "I3_14") (pintype "input"))
    )
    (net (code "108") (name "Net-(E36D-O)") (class "Default")
      (node (ref "E36") (pin "13") (pinfunction "O_13") (pintype "output"))
      (node (ref "E37") (pin "15") (pinfunction "I2_15") (pintype "input"))
    )
    (net (code "109") (name "Net-(E37A-Q0)") (class "Default")
      (node (ref "E37") (pin "5") (pinfunction "Q0_5") (pintype "output"))
      (node (ref "E38") (pin "3") (pinfunction "I_3") (pintype "input"))
    )
    (net (code "110") (name "Net-(E37A-Q1)") (class "Default")
      (node (ref "E37") (pin "7") (pinfunction "Q1_7") (pintype "output"))
      (node (ref "E38") (pin "5") (pinfunction "I_5") (pintype "input"))
    )
    (net (code "111") (name "Net-(E37A-Q2)") (class "Default")
      (node (ref "E37") (pin "9") (pinfunction "Q2_9") (pintype "output"))
      (node (ref "E38") (pin "11") (pinfunction "I_11") (pintype "input"))
    )
    (net (code "112") (name "Net-(E37A-Q3)") (class "Default")
      (node (ref "E37") (pin "11") (pinfunction "Q3_11") (pintype "output"))
      (node (ref "E38") (pin "9") (pinfunction "I_9") (pintype "input"))
    )
    (net (code "113") (name "Net-(E38A-I)") (class "Default")
      (node (ref "E38") (pin "1") (pinfunction "I_1") (pintype "input"))
      (node (ref "E38") (pin "8") (pinfunction "O_8") (pintype "output"))
    )
    (net (code "114") (name "Net-(E38B-O)") (class "Default")
      (node (ref "E38") (pin "4") (pinfunction "O_4") (pintype "output"))
      (node (ref "E41") (pin "5") (pinfunction "I_5") (pintype "input"))
    )
    (net (code "115") (name "Net-(E38C-O)") (class "Default")
      (node (ref "E38") (pin "6") (pinfunction "O_6") (pintype "output"))
      (node (ref "E41") (pin "9") (pinfunction "I_9") (pintype "input"))
    )
    (net (code "116") (name "Net-(E38E-O)") (class "Default")
      (node (ref "E38") (pin "10") (pinfunction "O_10") (pintype "output"))
      (node (ref "E38") (pin "13") (pinfunction "I_13") (pintype "input"))
    )
    (net (code "117") (name "Net-(E39A-I0)") (class "Default")
      (node (ref "E39") (pin "2") (pinfunction "I0_2") (pintype "input"))
      (node (ref "E40") (pin "5") (pinfunction "Q0_5") (pintype "output"))
    )
    (net (code "118") (name "Net-(E39B-I1)") (class "Default")
      (node (ref "E39") (pin "6") (pinfunction "I1_6") (pintype "input"))
      (node (ref "E40") (pin "7") (pinfunction "Q1_7") (pintype "output"))
    )
    (net (code "119") (name "Net-(E39C-I0)") (class "Default")
      (node (ref "E39") (pin "8") (pinfunction "I0_8") (pintype "input"))
      (node (ref "E40") (pin "9") (pinfunction "Q2_9") (pintype "output"))
    )
    (net (code "120") (name "Net-(E39D-I1)") (class "Default")
      (node (ref "E39") (pin "12") (pinfunction "I1_12") (pintype "input"))
      (node (ref "E40") (pin "11") (pinfunction "Q3_11") (pintype "output"))
    )
    (net (code "121") (name "Net-(E41A-I)") (class "Default")
      (node (ref "E41") (pin "1") (pinfunction "I_1") (pintype "input"))
      (node (ref "E44") (pin "10") (pinfunction "O_10") (pintype "output"))
    )
    (net (code "122") (name "Net-(E41B-I)") (class "Default")
      (node (ref "E41") (pin "3") (pinfunction "I_3") (pintype "input"))
      (node (ref "E44") (pin "12") (pinfunction "O_12") (pintype "output"))
    )
    (net (code "123") (name "Net-(E41E-I)") (class "Default")
      (node (ref "E41") (pin "11") (pinfunction "I_11") (pintype "input"))
      (node (ref "E44") (pin "8") (pinfunction "O_8") (pintype "output"))
    )
    (net (code "124") (name "Net-(E41F-I)") (class "Default")
      (node (ref "E41") (pin "13") (pinfunction "I_13") (pintype "input"))
      (node (ref "E44") (pin "6") (pinfunction "O_6") (pintype "output"))
    )
    (net (code "125") (name "Net-(E42A-O)") (class "Default")
      (node (ref "E42") (pin "3") (pinfunction "O_3") (pintype "output"))
      (node (ref "E43") (pin "3") (pinfunction "I0_3") (pintype "input"))
    )
    (net (code "126") (name "Net-(E42B-O)") (class "Default")
      (node (ref "E42") (pin "2") (pinfunction "O_2") (pintype "output"))
      (node (ref "E43") (pin "2") (pinfunction "I1_2") (pintype "input"))
    )
    (net (code "127") (name "Net-(E42C-O)") (class "Default")
      (node (ref "E42") (pin "14") (pinfunction "O_14") (pintype "output"))
      (node (ref "E43") (pin "14") (pinfunction "I3_14") (pintype "input"))
    )
    (net (code "128") (name "Net-(E42D-O)") (class "Default")
      (node (ref "E42") (pin "13") (pinfunction "O_13") (pintype "output"))
      (node (ref "E43") (pin "15") (pinfunction "I2_15") (pintype "input"))
    )
    (net (code "129") (name "Net-(E43A-Q0)") (class "Default")
      (node (ref "E43") (pin "5") (pinfunction "Q0_5") (pintype "output"))
      (node (ref "E44") (pin "5") (pinfunction "I_5") (pintype "input"))
    )
    (net (code "130") (name "Net-(E43A-Q1)") (class "Default")
      (node (ref "E43") (pin "7") (pinfunction "Q1_7") (pintype "output"))
      (node (ref "E44") (pin "9") (pinfunction "I_9") (pintype "input"))
    )
    (net (code "131") (name "Net-(E43A-Q2)") (class "Default")
      (node (ref "E43") (pin "9") (pinfunction "Q2_9") (pintype "output"))
      (node (ref "E44") (pin "13") (pinfunction "I_13") (pintype "input"))
    )
    (net (code "132") (name "Net-(E43A-Q3)") (class "Default")
      (node (ref "E43") (pin "11") (pinfunction "Q3_11") (pintype "output"))
      (node (ref "E44") (pin "11") (pinfunction "I_11") (pintype "input"))
    )
    (net (code "133") (name "Net-(Q1-B)") (class "Default")
      (node (ref "Q1") (pin "2") (pinfunction "B_2") (pintype "passive"))
      (node (ref "R20") (pin "2") (pinfunction "2_2") (pintype "passive"))
    )
    (net (code "134") (name "Net-(Q1-C)") (class "Default")
      (node (ref "Q1") (pin "3") (pinfunction "C_3") (pintype "passive"))
      (node (ref "R21") (pin "2") (pinfunction "2_2") (pintype "passive"))
    )
    (net (code "135") (name "Net-(Q2-B)") (class "Default")
      (node (ref "C57") (pin "-") (pinfunction "-_-") (pintype "passive"))
      (node (ref "Q2") (pin "2") (pinfunction "B_2") (pintype "passive"))
      (node (ref "R21") (pin "1") (pinfunction "1_1") (pintype "passive"))
      (node (ref "R22") (pin "1") (pinfunction "1_1") (pintype "passive"))
      (node (ref "R50") (pin "2") (pinfunction "2_2") (pintype "passive"))
    )
    (net (code "136") (name "Net-(Q2-E)") (class "Default")
      (node (ref "Q2") (pin "1") (pinfunction "E_1") (pintype "passive"))
      (node (ref "R19") (pin "1") (pinfunction "1_1") (pintype "passive"))
      (node (ref "R26") (pin "1") (pinfunction "1_1") (pintype "passive"))
      (node (ref "R31") (pin "1") (pinfunction "1_1") (pintype "passive"))
      (node (ref "W1") (pin "1") (pinfunction "1_1") (pintype "passive"))
      (node (ref "W2") (pin "1") (pinfunction "1_1") (pintype "passive"))
    )
    (net (code "137") (name "Net-(Q3-B)") (class "Default")
      (node (ref "Q3") (pin "2") (pinfunction "B_2") (pintype "passive"))
      (node (ref "R23") (pin "2") (pinfunction "2_2") (pintype "passive"))
    )
    (net (code "138") (name "Net-(Q3-C)") (class "Default")
      (node (ref "C58") (pin "-") (pinfunction "-_-") (pintype "passive"))
      (node (ref "D4") (pin "C") (pinfunction "C_C") (pintype "passive"))
      (node (ref "Q3") (pin "3") (pinfunction "C_3") (pintype "passive"))
      (node (ref "R24") (pin "2") (pinfunction "2_2") (pintype "passive"))
    )
    (net (code "139") (name "Net-(Q3-E)") (class "Default")
      (node (ref "Q3") (pin "1") (pinfunction "E_1") (pintype "passive"))
      (node (ref "Q4") (pin "3") (pinfunction "C_3") (pintype "passive"))
    )
    (net (code "140") (name "Net-(Q4-B)") (class "Default")
      (node (ref "C59") (pin "+") (pinfunction "+_+") (pintype "passive"))
      (node (ref "Q4") (pin "2") (pinfunction "B_2") (pintype "passive"))
      (node (ref "R45") (pin "2") (pinfunction "2_2") (pintype "passive"))
    )
    (net (code "141") (name "Net-(Q5-B)") (class "Default")
      (node (ref "C58") (pin "+") (pinfunction "+_+") (pintype "passive"))
      (node (ref "Q5") (pin "2") (pinfunction "B_2") (pintype "passive"))
      (node (ref "R25") (pin "2") (pinfunction "2_2") (pintype "passive"))
    )
    (net (code "142") (name "Net-(Q5-C)") (class "Default")
      (node (ref "D6") (pin "A") (pinfunction "A_A") (pintype "passive"))
      (node (ref "D7") (pin "C") (pinfunction "C_C") (pintype "passive"))
      (node (ref "Q5") (pin "3") (pinfunction "C_3") (pintype "passive"))
      (node (ref "Q6") (pin "2") (pinfunction "B_2") (pintype "passive"))
      (node (ref "R32") (pin "2") (pinfunction "2_2") (pintype "passive"))
    )
    (net (code "143") (name "Net-(Q7-B)") (class "Default")
      (node (ref "Q7") (pin "2") (pinfunction "B_2") (pintype "passive"))
      (node (ref "R2") (pin "2") (pinfunction "2_2") (pintype "passive"))
    )
    (net (code "144") (name "Net-(Q7-E)") (class "Default")
      (node (ref "Q7") (pin "1") (pinfunction "E_1") (pintype "passive"))
      (node (ref "Q8") (pin "1") (pinfunction "E_1") (pintype "passive"))
      (node (ref "R5") (pin "2") (pinfunction "2_2") (pintype "passive"))
    )
    (net (code "145") (name "Net-(Q8-C)") (class "Default")
      (node (ref "Q8") (pin "3") (pinfunction "C_3") (pintype "passive"))
      (node (ref "R4") (pin "1") (pinfunction "1_1") (pintype "passive"))
    )
    (net (code "146") (name "Net-(Q9-B)") (class "Default")
      (node (ref "C50") (pin "2") (pinfunction "2_2") (pintype "passive"))
      (node (ref "Q9") (pin "2") (pinfunction "B_2") (pintype "passive"))
      (node (ref "R11") (pin "2") (pinfunction "2_2") (pintype "passive"))
    )
    (net (code "147") (name "Net-(Q10-B)") (class "Default")
      (node (ref "Q10") (pin "2") (pinfunction "B_2") (pintype "passive"))
      (node (ref "Q9") (pin "3") (pinfunction "C_3") (pintype "passive"))
      (node (ref "R12") (pin "2") (pinfunction "2_2") (pintype "passive"))
      (node (ref "R9") (pin "1") (pinfunction "1_1") (pintype "passive"))
    )
    (net (code "148") (name "Net-(Q10-E)") (class "Default")
      (node (ref "Q10") (pin "1") (pinfunction "E_1") (pintype "passive"))
      (node (ref "Q9") (pin "1") (pinfunction "E_1") (pintype "passive"))
      (node (ref "R8") (pin "1") (pinfunction "1_1") (pintype "passive"))
    )
    (net (code "149") (name "Net-(R25-Pad1)") (class "Default")
      (node (ref "R25") (pin "1") (pinfunction "1_1") (pintype "passive"))
      (node (ref "R26") (pin "2") (pinfunction "2_2") (pintype "passive"))
      (node (ref "W1") (pin "2") (pinfunction "2_2") (pintype "passive"))
    )
    (net (code "150") (name "Net-(R27-S)") (class "Default")
      (node (ref "R27") (pin "2") (pinfunction "S_2") (pintype "passive"))
      (node (ref "R50") (pin "1") (pinfunction "1_1") (pintype "passive"))
    )
    (net (code "151") (name "Net-(R31-Pad2)") (class "Default")
      (node (ref "R31") (pin "2") (pinfunction "2_2") (pintype "passive"))
      (node (ref "R45") (pin "1") (pinfunction "1_1") (pintype "passive"))
      (node (ref "W2") (pin "2") (pinfunction "2_2") (pintype "passive"))
    )
    (net (code "152") (name "OUT_OF_TAPE") (class "Default")
      (node (ref "E23") (pin "8") (pinfunction "O_8") (pintype "output"))
      (node (ref "E26") (pin "11") (pinfunction "I_11") (pintype "input"))
      (node (ref "E5") (pin "9") (pinfunction "I0_9") (pintype "input"))
    )
    (net (code "153") (name "PIOP0") (class "Default")
      (node (ref "E22") (pin "5") (pinfunction "I1_5") (pintype "input"))
      (node (ref "E29") (pin "8") (pinfunction "O_8") (pintype "output"))
    )
    (net (code "154") (name "PIOP1") (class "Default")
      (node (ref "E18") (pin "2") (pinfunction "I0_2") (pintype "input"))
      (node (ref "E29") (pin "10") (pinfunction "O_10") (pintype "output"))
    )
    (net (code "155") (name "PIOP2") (class "Default")
      (node (ref "E13") (pin "5") (pinfunction "I1_5") (pintype "input"))
      (node (ref "E28") (pin "8") (pinfunction "O_8") (pintype "output"))
    )
    (net (code "156") (name "PIOP4") (class "Default")
      (node (ref "E22") (pin "13") (pinfunction "I1_13") (pintype "input"))
      (node (ref "E28") (pin "11") (pinfunction "O_11") (pintype "output"))
    )
    (net (code "157") (name "PLS") (class "Default")
      (node (ref "E27") (pin "4") (pinfunction "6_4") (pintype "output"))
      (node (ref "E28") (pin "10") (pinfunction "I1_10") (pintype "input"))
      (node (ref "E28") (pin "12") (pinfunction "I0_12") (pintype "input"))
      (node (ref "OMNIBUS") (pin "DB1") (pinfunction "1_DB1") (pintype "bidirectional"))
    )
    (net (code "158") (name "PN_HOLE1") (class "Default")
      (node (ref "E41") (pin "12") (pinfunction "O_12") (pintype "output"))
      (node (ref "J1") (pin "LL") (pinfunction "P_LL") (pintype "passive"))
    )
    (net (code "159") (name "PN_HOLE2") (class "Default")
      (node (ref "E41") (pin "10") (pinfunction "O_10") (pintype "output"))
      (node (ref "J1") (pin "JJ") (pinfunction "P_JJ") (pintype "passive"))
    )
    (net (code "160") (name "PN_HOLE3") (class "Default")
      (node (ref "E41") (pin "2") (pinfunction "O_2") (pintype "output"))
      (node (ref "J1") (pin "FF") (pinfunction "P_FF") (pintype "passive"))
    )
    (net (code "161") (name "PN_HOLE4") (class "Default")
      (node (ref "E41") (pin "4") (pinfunction "O_4") (pintype "output"))
      (node (ref "J1") (pin "DD") (pinfunction "P_DD") (pintype "passive"))
    )
    (net (code "162") (name "PN_HOLE5") (class "Default")
      (node (ref "E41") (pin "6") (pinfunction "O_6") (pintype "output"))
      (node (ref "J1") (pin "Z") (pinfunction "P_Z") (pintype "passive"))
    )
    (net (code "163") (name "PN_HOLE6") (class "Default")
      (node (ref "E41") (pin "8") (pinfunction "O_8") (pintype "output"))
      (node (ref "J1") (pin "X") (pinfunction "P_X") (pintype "passive"))
    )
    (net (code "164") (name "PN_HOLE7") (class "Default")
      (node (ref "E38") (pin "2") (pinfunction "O_2") (pintype "output"))
      (node (ref "J1") (pin "V") (pinfunction "P_V") (pintype "passive"))
    )
    (net (code "165") (name "PN_HOLE8") (class "Default")
      (node (ref "E38") (pin "12") (pinfunction "O_12") (pintype "output"))
      (node (ref "J1") (pin "T") (pinfunction "P_T") (pintype "passive"))
    )
    (net (code "166") (name "PUNCH_DONE") (class "Default")
      (node (ref "E26") (pin "12") (pinfunction "O_12") (pintype "output"))
      (node (ref "J1") (pin "N") (pinfunction "P_N") (pintype "passive"))
    )
    (net (code "167") (name "PUNCH_FLAG") (class "Default")
      (node (ref "E10") (pin "9") (pinfunction "Q_9") (pintype "output"))
      (node (ref "E18") (pin "12") (pinfunction "I1_12") (pintype "input"))
      (node (ref "E18") (pin "3") (pinfunction "I1_3") (pintype "input"))
    )
    (net (code "168") (name "PUNCH_SYNC") (class "Default")
      (node (ref "J1") (pin "J") (pinfunction "P_J") (pintype "passive"))
      (node (ref "R11") (pin "1") (pinfunction "1_1") (pintype "passive"))
    )
    (net (code "169") (name "PUN_TO_SPEED") (class "Default")
      (node (ref "E13") (pin "13") (pinfunction "I1_13") (pintype "input"))
      (node (ref "J1") (pin "R") (pinfunction "P_R") (pintype "passive"))
      (node (ref "R36") (pin "2") (pinfunction "2_2") (pintype "passive"))
      (node (ref "R37") (pin "2") (pinfunction "2_2") (pintype "passive"))
    )
    (net (code "170") (name "RDATA_STROBE") (class "Default")
      (node (ref "E12") (pin "11") (pinfunction "CLK_11") (pintype "input"))
      (node (ref "E2") (pin "3") (pinfunction "CLK_3") (pintype "input"))
      (node (ref "E26") (pin "5") (pinfunction "I_5") (pintype "input"))
      (node (ref "E44") (pin "4") (pinfunction "O_4") (pintype "output"))
    )
    (net (code "171") (name "RDATA_TO_BUS") (class "Default")
      (node (ref "E17") (pin "8") (pinfunction "I0_8") (pintype "input"))
      (node (ref "E17") (pin "9") (pinfunction "I1_9") (pintype "input"))
      (node (ref "E22") (pin "1") (pinfunction "I0_1") (pintype "input"))
      (node (ref "E28") (pin "3") (pinfunction "O_3") (pintype "output"))
      (node (ref "E33") (pin "11") (pinfunction "I0_11") (pintype "input"))
      (node (ref "E33") (pin "3") (pinfunction "I1_3") (pintype "input"))
      (node (ref "E33") (pin "6") (pinfunction "I1_6") (pintype "input"))
      (node (ref "E33") (pin "8") (pinfunction "I0_8") (pintype "input"))
      (node (ref "E39") (pin "11") (pinfunction "I0_11") (pintype "input"))
      (node (ref "E39") (pin "3") (pinfunction "I1_3") (pintype "input"))
      (node (ref "E39") (pin "5") (pinfunction "I0_5") (pintype "input"))
      (node (ref "E39") (pin "9") (pinfunction "I1_9") (pintype "input"))
      (node (ref "OMNIBUS") (pin "DA1") (pinfunction "1_DA1") (pintype "bidirectional"))
    )
    (net (code "172") (name "RDR_RUN") (class "Default")
      (node (ref "E11") (pin "4") (pinfunction "I1_4") (pintype "input"))
      (node (ref "E12") (pin "12") (pinfunction "D_12") (pintype "input"))
      (node (ref "E2") (pin "5") (pinfunction "Q_5") (pintype "output"))
    )
    (net (code "173") (name "RD_HOLE1") (class "Default")
      (node (ref "E40") (pin "14") (pinfunction "I3_14") (pintype "input"))
      (node (ref "J2") (pin "L") (pinfunction "P_L") (pintype "passive"))
    )
    (net (code "174") (name "RD_HOLE2") (class "Default")
      (node (ref "E40") (pin "15") (pinfunction "I2_15") (pintype "input"))
      (node (ref "J2") (pin "N") (pinfunction "P_N") (pintype "passive"))
    )
    (net (code "175") (name "RD_HOLE3") (class "Default")
      (node (ref "E40") (pin "2") (pinfunction "I1_2") (pintype "input"))
      (node (ref "J2") (pin "R") (pinfunction "P_R") (pintype "passive"))
    )
    (net (code "176") (name "RD_HOLE4") (class "Default")
      (node (ref "E40") (pin "3") (pinfunction "I0_3") (pintype "input"))
      (node (ref "J2") (pin "T") (pinfunction "P_T") (pintype "passive"))
    )
    (net (code "177") (name "RD_HOLE5") (class "Default")
      (node (ref "E34") (pin "14") (pinfunction "I3_14") (pintype "input"))
      (node (ref "J2") (pin "V") (pinfunction "P_V") (pintype "passive"))
    )
    (net (code "178") (name "RD_HOLE6") (class "Default")
      (node (ref "E34") (pin "15") (pinfunction "I2_15") (pintype "input"))
      (node (ref "J2") (pin "X") (pinfunction "P_X") (pintype "passive"))
    )
    (net (code "179") (name "RD_HOLE7") (class "Default")
      (node (ref "E34") (pin "2") (pinfunction "I1_2") (pintype "input"))
      (node (ref "J2") (pin "Z") (pinfunction "P_Z") (pintype "passive"))
    )
    (net (code "180") (name "RD_HOLE8") (class "Default")
      (node (ref "E34") (pin "3") (pinfunction "I0_3") (pintype "input"))
      (node (ref "J2") (pin "BB") (pinfunction "P_BB") (pintype "passive"))
    )
    (net (code "181") (name "RIOP0") (class "Default")
      (node (ref "E22") (pin "9") (pinfunction "I0_9") (pintype "input"))
      (node (ref "E29") (pin "4") (pinfunction "O_4") (pintype "output"))
    )
    (net (code "182") (name "RIOP1") (class "Default")
      (node (ref "E18") (pin "6") (pinfunction "I1_6") (pintype "input"))
      (node (ref "E29") (pin "2") (pinfunction "O_2") (pintype "output"))
    )
    (net (code "183") (name "ROTATE_PULSE") (class "Default")
      (node (ref "E6") (pin "6") (pinfunction "O_6") (pintype "output"))
      (node (ref "E9") (pin "11") (pinfunction "CLK_11") (pintype "input"))
      (node (ref "E9") (pin "3") (pinfunction "CLK_3") (pintype "input"))
    )
    (net (code "184") (name "SCR_ACTIVE") (class "Default")
      (node (ref "J1") (pin "F") (pinfunction "P_F") (pintype "passive"))
      (node (ref "R46") (pin "2") (pinfunction "2_2") (pintype "passive"))
    )
    (net (code "185") (name "TP3") (class "Default")
      (node (ref "E24") (pin "12") (pinfunction "I1_12") (pintype "input"))
      (node (ref "OMNIBUS") (pin "CH2") (pinfunction "1_CH2") (pintype "bidirectional"))
    )
    (net (code "186") (name "VCC") (class "Default")
      (node (ref "C1") (pin "1") (pinfunction "1_1") (pintype "passive"))
      (node (ref "C10") (pin "1") (pinfunction "1_1") (pintype "passive"))
      (node (ref "C11") (pin "1") (pinfunction "1_1") (pintype "passive"))
      (node (ref "C12") (pin "1") (pinfunction "1_1") (pintype "passive"))
      (node (ref "C13") (pin "1") (pinfunction "1_1") (pintype "passive"))
      (node (ref "C14") (pin "1") (pinfunction "1_1") (pintype "passive"))
      (node (ref "C15") (pin "1") (pinfunction "1_1") (pintype "passive"))
      (node (ref "C16") (pin "1") (pinfunction "1_1") (pintype "passive"))
      (node (ref "C17") (pin "1") (pinfunction "1_1") (pintype "passive"))
      (node (ref "C18") (pin "1") (pinfunction "1_1") (pintype "passive"))
      (node (ref "C19") (pin "1") (pinfunction "1_1") (pintype "passive"))
      (node (ref "C2") (pin "1") (pinfunction "1_1") (pintype "passive"))
      (node (ref "C20") (pin "1") (pinfunction "1_1") (pintype "passive"))
      (node (ref "C21") (pin "1") (pinfunction "1_1") (pintype "passive"))
      (node (ref "C23") (pin "1") (pinfunction "1_1") (pintype "passive"))
      (node (ref "C24") (pin "1") (pinfunction "1_1") (pintype "passive"))
      (node (ref "C25") (pin "1") (pinfunction "1_1") (pintype "passive"))
      (node (ref "C26") (pin "1") (pinfunction "1_1") (pintype "passive"))
      (node (ref "C27") (pin "1") (pinfunction "1_1") (pintype "passive"))
      (node (ref "C28") (pin "1") (pinfunction "1_1") (pintype "passive"))
      (node (ref "C29") (pin "1") (pinfunction "1_1") (pintype "passive"))
      (node (ref "C3") (pin "1") (pinfunction "1_1") (pintype "passive"))
      (node (ref "C30") (pin "1") (pinfunction "1_1") (pintype "passive"))
      (node (ref "C33") (pin "1") (pinfunction "1_1") (pintype "passive"))
      (node (ref "C34") (pin "1") (pinfunction "1_1") (pintype "passive"))
      (node (ref "C35") (pin "1") (pinfunction "1_1") (pintype "passive"))
      (node (ref "C36") (pin "1") (pinfunction "1_1") (pintype "passive"))
      (node (ref "C37") (pin "1") (pinfunction "1_1") (pintype "passive"))
      (node (ref "C38") (pin "1") (pinfunction "1_1") (pintype "passive"))
      (node (ref "C39") (pin "1") (pinfunction "1_1") (pintype "passive"))
      (node (ref "C4") (pin "1") (pinfunction "1_1") (pintype "passive"))
      (node (ref "C40") (pin "1") (pinfunction "1_1") (pintype "passive"))
      (node (ref "C41") (pin "1") (pinfunction "1_1") (pintype "passive"))
      (node (ref "C42") (pin "1") (pinfunction "1_1") (pintype "passive"))
      (node (ref "C43") (pin "1") (pinfunction "1_1") (pintype "passive"))
      (node (ref "C44") (pin "1") (pinfunction "1_1") (pintype "passive"))
      (node (ref "C45") (pin "+") (pinfunction "+_+") (pintype "passive"))
      (node (ref "C46") (pin "+") (pinfunction "+_+") (pintype "passive"))
      (node (ref "C47") (pin "+") (pinfunction "+_+") (pintype "passive"))
      (node (ref "C5") (pin "1") (pinfunction "1_1") (pintype "passive"))
      (node (ref "C50") (pin "1") (pinfunction "1_1") (pintype "passive"))
      (node (ref "C6") (pin "1") (pinfunction "1_1") (pintype "passive"))
      (node (ref "C7") (pin "1") (pinfunction "1_1") (pintype "passive"))
      (node (ref "C8") (pin "1") (pinfunction "1_1") (pintype "passive"))
      (node (ref "C9") (pin "1") (pinfunction "1_1") (pintype "passive"))
      (node (ref "OMNIBUS") (pin "AA2") (pinfunction "1_AA2") (pintype "bidirectional"))
      (node (ref "OMNIBUS") (pin "BA2") (pinfunction "1_BA2") (pintype "bidirectional"))
      (node (ref "OMNIBUS") (pin "CA2") (pinfunction "1_CA2") (pintype "bidirectional"))
      (node (ref "R10") (pin "2") (pinfunction "2_2") (pintype "passive"))
      (node (ref "R14") (pin "2") (pinfunction "2_2") (pintype "passive"))
      (node (ref "R15") (pin "2") (pinfunction "2_2") (pintype "passive"))
      (node (ref "R16") (pin "2") (pinfunction "2_2") (pintype "passive"))
      (node (ref "R17") (pin "2") (pinfunction "2_2") (pintype "passive"))
      (node (ref "R19") (pin "2") (pinfunction "2_2") (pintype "passive"))
      (node (ref "R28") (pin "2") (pinfunction "2_2") (pintype "passive"))
      (node (ref "R3") (pin "2") (pinfunction "2_2") (pintype "passive"))
      (node (ref "R30") (pin "2") (pinfunction "2_2") (pintype "passive"))
      (node (ref "R33") (pin "2") (pinfunction "2_2") (pintype "passive"))
      (node (ref "R37") (pin "1") (pinfunction "1_1") (pintype "passive"))
      (node (ref "R4") (pin "2") (pinfunction "2_2") (pintype "passive"))
      (node (ref "R40") (pin "2") (pinfunction "2_2") (pintype "passive"))
      (node (ref "R41") (pin "2") (pinfunction "2_2") (pintype "passive"))
      (node (ref "R42") (pin "2") (pinfunction "2_2") (pintype "passive"))
      (node (ref "R43") (pin "2") (pinfunction "2_2") (pintype "passive"))
      (node (ref "R47") (pin "2") (pinfunction "2_2") (pintype "passive"))
      (node (ref "R48") (pin "2") (pinfunction "2_2") (pintype "passive"))
      (node (ref "R49") (pin "2") (pinfunction "2_2") (pintype "passive"))
      (node (ref "R52") (pin "2") (pinfunction "2_2") (pintype "passive"))
      (node (ref "R7") (pin "2") (pinfunction "2_2") (pintype "passive"))
      (node (ref "R8") (pin "2") (pinfunction "2_2") (pintype "passive"))
      (node (ref "R9") (pin "2") (pinfunction "2_2") (pintype "passive"))
    )
    (net (code "187") (name "unconnected-(E2B-Q-Pad9)") (class "Default")
      (node (ref "E2") (pin "9") (pinfunction "Q_9") (pintype "output"))
    )
    (net (code "188") (name "unconnected-(E4A-Q-Pad8)") (class "Default")
      (node (ref "E4") (pin "8") (pinfunction "Q_8") (pintype "output"))
    )
    (net (code "189") (name "unconnected-(E10A-Q-Pad5)") (class "Default")
      (node (ref "E10") (pin "5") (pinfunction "Q_5") (pintype "output"))
    )
    (net (code "190") (name "unconnected-(E10B-~{Q}-Pad8)") (class "Default")
      (node (ref "E10") (pin "8") (pinfunction "~{Q}_8") (pintype "output"))
    )
    (net (code "191") (name "unconnected-(E12A-Q-Pad5)") (class "Default")
      (node (ref "E12") (pin "5") (pinfunction "Q_5") (pintype "output"))
    )
    (net (code "192") (name "unconnected-(E12B-~{Q}-Pad8)") (class "Default")
      (node (ref "E12") (pin "8") (pinfunction "~{Q}_8") (pintype "output"))
    )
    (net (code "193") (name "unconnected-(E14A-~{Q}-Pad6)") (class "Default")
      (node (ref "E14") (pin "6") (pinfunction "~{Q}_6") (pintype "output"))
    )
    (net (code "194") (name "unconnected-(E14B-Q-Pad9)") (class "Default")
      (node (ref "E14") (pin "9") (pinfunction "Q_9") (pintype "output"))
    )
    (net (code "195") (name "unconnected-(E15A-Q-Pad8)") (class "Default")
      (node (ref "E15") (pin "8") (pinfunction "Q_8") (pintype "output"))
    )
    (net (code "196") (name "unconnected-(E19A-~{Q}-Pad6)") (class "Default")
      (node (ref "E19") (pin "6") (pinfunction "~{Q}_6") (pintype "output"))
    )
    (net (code "197") (name "unconnected-(E27A-3-Pad10)") (class "Default")
      (node (ref "E27") (pin "10") (pinfunction "3_10") (pintype "output"))
    )
    (net (code "198") (name "unconnected-(E27A-5-Pad3)") (class "Default")
      (node (ref "E27") (pin "3") (pinfunction "5_3") (pintype "output"))
    )
    (net (code "199") (name "unconnected-(E27A-7-Pad5)") (class "Default")
      (node (ref "E27") (pin "5") (pinfunction "7_5") (pintype "output"))
    )
    (net (code "200") (name "unconnected-(E27A-8-Pad6)") (class "Default")
      (node (ref "E27") (pin "6") (pinfunction "8_6") (pintype "output"))
    )
    (net (code "201") (name "unconnected-(E27A-9-Pad7)") (class "Default")
      (node (ref "E27") (pin "7") (pinfunction "9_7") (pintype "output"))
    )
    (net (code "202") (name "unconnected-(E31A-3-Pad10)") (class "Default")
      (node (ref "E31") (pin "10") (pinfunction "3_10") (pintype "output"))
    )
    (net (code "203") (name "unconnected-(E31A-5-Pad3)") (class "Default")
      (node (ref "E31") (pin "3") (pinfunction "5_3") (pintype "output"))
    )
    (net (code "204") (name "unconnected-(E31A-7-Pad5)") (class "Default")
      (node (ref "E31") (pin "5") (pinfunction "7_5") (pintype "output"))
    )
    (net (code "205") (name "unconnected-(E31A-8-Pad6)") (class "Default")
      (node (ref "E31") (pin "6") (pinfunction "8_6") (pintype "output"))
    )
    (net (code "206") (name "unconnected-(E31A-9-Pad7)") (class "Default")
      (node (ref "E31") (pin "7") (pinfunction "9_7") (pintype "output"))
    )
    (net (code "207") (name "unconnected-(E34A-Q4-Pad12)") (class "Default")
      (node (ref "E34") (pin "12") (pinfunction "Q4_12") (pintype "output"))
    )
    (net (code "208") (name "unconnected-(E37A-Q4-Pad12)") (class "Default")
      (node (ref "E37") (pin "12") (pinfunction "Q4_12") (pintype "output"))
    )
    (net (code "209") (name "unconnected-(E40A-Q4-Pad12)") (class "Default")
      (node (ref "E40") (pin "12") (pinfunction "Q4_12") (pintype "output"))
    )
    (net (code "210") (name "unconnected-(E43A-Q4-Pad12)") (class "Default")
      (node (ref "E43") (pin "12") (pinfunction "Q4_12") (pintype "output"))
    )
    (net (code "211") (name "~{AB}") (class "Default")
      (node (ref "E11") (pin "1") (pinfunction "I0_1") (pintype "input"))
      (node (ref "E32") (pin "5") (pinfunction "I1_5") (pintype "input"))
      (node (ref "E6") (pin "8") (pinfunction "O_8") (pintype "output"))
    )
    (net (code "212") (name "~{BA}") (class "Default")
      (node (ref "E3") (pin "4") (pinfunction "O_4") (pintype "output"))
      (node (ref "J2") (pin "FF") (pinfunction "P_FF") (pintype "passive"))
    )
    (net (code "213") (name "~{BB}") (class "Default")
      (node (ref "E3") (pin "2") (pinfunction "O_2") (pintype "output"))
      (node (ref "J2") (pin "LL") (pinfunction "P_LL") (pintype "passive"))
    )
    (net (code "214") (name "~{C1}") (class "Default")
      (node (ref "E17") (pin "10") (pinfunction "O_10") (pintype "open_collector"))
      (node (ref "OMNIBUS") (pin "CH1") (pinfunction "1_CH1") (pintype "bidirectional"))
    )
    (net (code "215") (name "~{CATCH_PULSE}") (class "Default")
      (node (ref "E6") (pin "11") (pinfunction "O_11") (pintype "output"))
      (node (ref "E6") (pin "4") (pinfunction "I0_4") (pintype "input"))
    )
    (net (code "216") (name "~{CLOCK_PULSE}") (class "Default")
      (node (ref "E11") (pin "3") (pinfunction "I0_3") (pintype "input"))
      (node (ref "E5") (pin "3") (pinfunction "O_3") (pintype "output"))
      (node (ref "E8") (pin "11") (pinfunction "I_11") (pintype "input"))
    )
    (net (code "217") (name "~{DATA04}") (class "Default")
      (node (ref "E33") (pin "1") (pinfunction "O_1") (pintype "open_collector"))
      (node (ref "E36") (pin "12") (pinfunction "I1_12") (pintype "input"))
      (node (ref "OMNIBUS") (pin "BR1") (pinfunction "1_BR1") (pintype "bidirectional"))
    )
    (net (code "218") (name "~{DATA05}") (class "Default")
      (node (ref "E33") (pin "4") (pinfunction "O_4") (pintype "open_collector"))
      (node (ref "E36") (pin "9") (pinfunction "I0_9") (pintype "input"))
      (node (ref "OMNIBUS") (pin "BS1") (pinfunction "1_BS1") (pintype "bidirectional"))
    )
    (net (code "219") (name "~{DATA06}") (class "Default")
      (node (ref "E33") (pin "13") (pinfunction "O_13") (pintype "open_collector"))
      (node (ref "E36") (pin "7") (pinfunction "I1_7") (pintype "input"))
      (node (ref "OMNIBUS") (pin "BU1") (pinfunction "1_BU1") (pintype "bidirectional"))
    )
    (net (code "220") (name "~{DATA07}") (class "Default")
      (node (ref "E33") (pin "10") (pinfunction "O_10") (pintype "open_collector"))
      (node (ref "E36") (pin "4") (pinfunction "I0_4") (pintype "input"))
      (node (ref "OMNIBUS") (pin "BV1") (pinfunction "1_BV1") (pintype "bidirectional"))
    )
    (net (code "221") (name "~{DATA08}") (class "Default")
      (node (ref "E39") (pin "1") (pinfunction "O_1") (pintype "open_collector"))
      (node (ref "E42") (pin "12") (pinfunction "I1_12") (pintype "input"))
      (node (ref "OMNIBUS") (pin "DR1") (pinfunction "1_DR1") (pintype "bidirectional"))
    )
    (net (code "222") (name "~{DATA09}") (class "Default")
      (node (ref "E39") (pin "4") (pinfunction "O_4") (pintype "open_collector"))
      (node (ref "E42") (pin "9") (pinfunction "I0_9") (pintype "input"))
      (node (ref "OMNIBUS") (pin "DS1") (pinfunction "1_DS1") (pintype "bidirectional"))
    )
    (net (code "223") (name "~{DATA10}") (class "Default")
      (node (ref "E39") (pin "10") (pinfunction "O_10") (pintype "open_collector"))
      (node (ref "E42") (pin "7") (pinfunction "I1_7") (pintype "input"))
      (node (ref "OMNIBUS") (pin "DU1") (pinfunction "1_DU1") (pintype "bidirectional"))
    )
    (net (code "224") (name "~{DATA11}") (class "Default")
      (node (ref "E39") (pin "13") (pinfunction "O_13") (pintype "open_collector"))
      (node (ref "E42") (pin "4") (pinfunction "I0_4") (pintype "input"))
      (node (ref "OMNIBUS") (pin "DV1") (pinfunction "1_DV1") (pintype "bidirectional"))
    )
    (net (code "225") (name "~{ENABLE}") (class "Default")
      (node (ref "E26") (pin "4") (pinfunction "O_4") (pintype "output"))
      (node (ref "R23") (pin "1") (pinfunction "1_1") (pintype "passive"))
    )
    (net (code "226") (name "~{ENA_PUN_BUFFR}") (class "Default")
      (node (ref "E16") (pin "13") (pinfunction "O_13") (pintype "output"))
      (node (ref "E36") (pin "10") (pinfunction "I1_10") (pintype "input"))
      (node (ref "E36") (pin "11") (pinfunction "I0_11") (pintype "input"))
      (node (ref "E36") (pin "5") (pinfunction "I1_5") (pintype "input"))
      (node (ref "E36") (pin "6") (pinfunction "I0_6") (pintype "input"))
      (node (ref "E42") (pin "10") (pinfunction "I1_10") (pintype "input"))
      (node (ref "E42") (pin "11") (pinfunction "I0_11") (pintype "input"))
      (node (ref "E42") (pin "5") (pinfunction "I1_5") (pintype "input"))
      (node (ref "E42") (pin "6") (pinfunction "I0_6") (pintype "input"))
    )
    (net (code "227") (name "~{INIT+EOT}") (class "Default")
      (node (ref "E1") (pin "13") (pinfunction "I2_13") (pintype "input"))
      (node (ref "E2") (pin "1") (pinfunction "CLR_1") (pintype "input"))
      (node (ref "E8") (pin "6") (pinfunction "O_6") (pintype "output"))
    )
    (net (code "228") (name "~{INITIALIZE}") (class "Default")
      (node (ref "E10") (pin "1") (pinfunction "CLR_1") (pintype "input"))
      (node (ref "E14") (pin "4") (pinfunction "PRE_4") (pintype "input"))
      (node (ref "E2") (pin "13") (pinfunction "CLR_13") (pintype "input"))
      (node (ref "E30") (pin "2") (pinfunction "O_2") (pintype "output"))
      (node (ref "E35") (pin "10") (pinfunction "I1_10") (pintype "input"))
      (node (ref "E35") (pin "9") (pinfunction "I0_9") (pintype "input"))
      (node (ref "E5") (pin "5") (pinfunction "I1_5") (pintype "input"))
    )
    (net (code "229") (name "~{INTERNAL_IO}") (class "Default")
      (node (ref "E17") (pin "1") (pinfunction "O_1") (pintype "open_collector"))
      (node (ref "E17") (pin "4") (pinfunction "O_4") (pintype "open_collector"))
      (node (ref "OMNIBUS") (pin "CL1") (pinfunction "1_CL1") (pintype "bidirectional"))
    )
    (net (code "230") (name "~{INTERRUPT}") (class "Default")
      (node (ref "E18") (pin "10") (pinfunction "O_10") (pintype "open_collector"))
      (node (ref "E18") (pin "13") (pinfunction "O_13") (pintype "open_collector"))
      (node (ref "OMNIBUS") (pin "CP1") (pinfunction "1_CP1") (pintype "bidirectional"))
    )
    (net (code "231") (name "~{MD3}") (class "Default")
      (node (ref "E24") (pin "9") (pinfunction "I0_9") (pintype "input"))
      (node (ref "OMNIBUS") (pin "AP1") (pinfunction "1_AP1") (pintype "bidirectional"))
    )
    (net (code "232") (name "~{MD4}") (class "Default")
      (node (ref "E20") (pin "12") (pinfunction "I1_12") (pintype "input"))
      (node (ref "OMNIBUS") (pin "BK1") (pinfunction "1_BK1") (pintype "bidirectional"))
    )
    (net (code "233") (name "~{MD5}") (class "Default")
      (node (ref "E20") (pin "9") (pinfunction "I0_9") (pintype "input"))
      (node (ref "OMNIBUS") (pin "BL1") (pinfunction "1_BL1") (pintype "bidirectional"))
    )
    (net (code "234") (name "~{MD6}") (class "Default")
      (node (ref "E20") (pin "7") (pinfunction "I1_7") (pintype "input"))
      (node (ref "OMNIBUS") (pin "BM1") (pinfunction "1_BM1") (pintype "bidirectional"))
    )
    (net (code "235") (name "~{MD7}") (class "Default")
      (node (ref "E20") (pin "4") (pinfunction "I0_4") (pintype "input"))
      (node (ref "E25") (pin "10") (pinfunction "I4_10") (pintype "input"))
      (node (ref "OMNIBUS") (pin "BP1") (pinfunction "1_BP1") (pintype "bidirectional"))
    )
    (net (code "236") (name "~{MD8}") (class "Default")
      (node (ref "E21") (pin "11") (pinfunction "I5_11") (pintype "input"))
      (node (ref "E24") (pin "7") (pinfunction "I1_7") (pintype "input"))
      (node (ref "OMNIBUS") (pin "DK1") (pinfunction "1_DK1") (pintype "bidirectional"))
    )
    (net (code "237") (name "~{MD9}") (class "Default")
      (node (ref "E30") (pin "12") (pinfunction "I1_12") (pintype "input"))
      (node (ref "OMNIBUS") (pin "DL1") (pinfunction "1_DL1") (pintype "bidirectional"))
    )
    (net (code "238") (name "~{MD10}") (class "Default")
      (node (ref "E30") (pin "9") (pinfunction "I0_9") (pintype "input"))
      (node (ref "OMNIBUS") (pin "DM1") (pinfunction "1_DM1") (pintype "bidirectional"))
    )
    (net (code "239") (name "~{MD11}") (class "Default")
      (node (ref "E30") (pin "4") (pinfunction "I0_4") (pintype "input"))
      (node (ref "OMNIBUS") (pin "DP1") (pinfunction "1_DP1") (pintype "bidirectional"))
    )
    (net (code "240") (name "~{MOTOR_STOPPING}") (class "Default")
      (node (ref "E11") (pin "5") (pinfunction "I2_5") (pintype "input"))
      (node (ref "E12") (pin "3") (pinfunction "CLK_3") (pintype "input"))
      (node (ref "E4") (pin "6") (pinfunction "~{Q}_6") (pintype "output"))
      (node (ref "OMNIBUS") (pin "BA1") (pinfunction "1_BA1") (pintype "bidirectional"))
    )
    (net (code "241") (name "~{MULTI_OUT}") (class "Default")
      (node (ref "D6") (pin "C") (pinfunction "C_C") (pintype "passive"))
      (node (ref "E3") (pin "11") (pinfunction "I_11") (pintype "input"))
      (node (ref "Q6") (pin "1") (pinfunction "E_1") (pintype "passive"))
      (node (ref "R34") (pin "1") (pinfunction "1_1") (pintype "passive"))
      (node (ref "R35") (pin "1") (pinfunction "1_1") (pintype "passive"))
      (node (ref "R44") (pin "2") (pinfunction "2_2") (pintype "passive"))
    )
    (net (code "242") (name "~{PAUSE}") (class "Default")
      (node (ref "E16") (pin "7") (pinfunction "I1_7") (pintype "input"))
      (node (ref "OMNIBUS") (pin "CD1") (pinfunction "1_CD1") (pintype "bidirectional"))
    )
    (net (code "243") (name "~{PCE}") (class "Default")
      (node (ref "E27") (pin "13") (pinfunction "0_13") (pintype "output"))
      (node (ref "E29") (pin "9") (pinfunction "I_9") (pintype "input"))
    )
    (net (code "244") (name "~{PCF}") (class "Default")
      (node (ref "E27") (pin "11") (pinfunction "2_11") (pintype "output"))
      (node (ref "E28") (pin "9") (pinfunction "I0_9") (pintype "input"))
    )
    (net (code "245") (name "~{PPC}") (class "Default")
      (node (ref "E27") (pin "9") (pinfunction "4_9") (pintype "output"))
      (node (ref "E28") (pin "13") (pinfunction "I1_13") (pintype "input"))
    )
    (net (code "246") (name "~{PSF}") (class "Default")
      (node (ref "E27") (pin "12") (pinfunction "1_12") (pintype "output"))
      (node (ref "E29") (pin "11") (pinfunction "I_11") (pintype "input"))
    )
    (net (code "247") (name "~{PUNCH_DONE}") (class "Default")
      (node (ref "E10") (pin "3") (pinfunction "CLK_3") (pintype "input"))
      (node (ref "E14") (pin "10") (pinfunction "PRE_10") (pintype "input"))
      (node (ref "E15") (pin "6") (pinfunction "~{Q}_6") (pintype "output"))
      (node (ref "E26") (pin "13") (pinfunction "I_13") (pintype "input"))
    )
    (net (code "248") (name "~{PUNCH_FEED}") (class "Default")
      (node (ref "C64") (pin "1") (pinfunction "1_1") (pintype "passive"))
      (node (ref "E13") (pin "1") (pinfunction "I0_1") (pintype "input"))
      (node (ref "E37") (pin "1") (pinfunction "R_1") (pintype "input"))
      (node (ref "E43") (pin "1") (pinfunction "R_1") (pintype "input"))
      (node (ref "J1") (pin "D") (pinfunction "P_D") (pintype "passive"))
      (node (ref "R7") (pin "1") (pinfunction "1_1") (pintype "passive"))
    )
    (net (code "249") (name "~{PUNCH_STROBE}") (class "Default")
      (node (ref "E10") (pin "4") (pinfunction "PRE_4") (pintype "input"))
      (node (ref "E22") (pin "11") (pinfunction "O_11") (pintype "output"))
      (node (ref "E37") (pin "6") (pinfunction "C_6") (pintype "input"))
      (node (ref "E43") (pin "6") (pinfunction "C_6") (pintype "input"))
    )
    (net (code "250") (name "~{RBC}") (class "Default")
      (node (ref "E28") (pin "1") (pinfunction "I0_1") (pintype "input"))
      (node (ref "E28") (pin "4") (pinfunction "I0_4") (pintype "input"))
      (node (ref "E31") (pin "4") (pinfunction "6_4") (pintype "output"))
    )
    (net (code "251") (name "~{RDR_RUN}") (class "Default")
      (node (ref "E11") (pin "13") (pinfunction "I2_13") (pintype "input"))
      (node (ref "E2") (pin "6") (pinfunction "~{Q}_6") (pintype "output"))
    )
    (net (code "252") (name "~{RFC}") (class "Default")
      (node (ref "E28") (pin "5") (pinfunction "I1_5") (pintype "input"))
      (node (ref "E31") (pin "9") (pinfunction "4_9") (pintype "output"))
    )
    (net (code "253") (name "~{RIOP2}") (class "Default")
      (node (ref "E1") (pin "1") (pinfunction "I0_1") (pintype "input"))
      (node (ref "E22") (pin "3") (pinfunction "O_3") (pintype "output"))
    )
    (net (code "254") (name "~{RIOP4}") (class "Default")
      (node (ref "E1") (pin "2") (pinfunction "I1_2") (pintype "input"))
      (node (ref "E11") (pin "8") (pinfunction "O_8") (pintype "output"))
      (node (ref "E2") (pin "4") (pinfunction "PRE_4") (pintype "input"))
    )
    (net (code "255") (name "~{RPE}") (class "Default")
      (node (ref "E29") (pin "3") (pinfunction "I_3") (pintype "input"))
      (node (ref "E31") (pin "13") (pinfunction "0_13") (pintype "output"))
    )
    (net (code "256") (name "~{RRB}") (class "Default")
      (node (ref "E28") (pin "2") (pinfunction "I1_2") (pintype "input"))
      (node (ref "E31") (pin "11") (pinfunction "2_11") (pintype "output"))
    )
    (net (code "257") (name "~{RSF}") (class "Default")
      (node (ref "E29") (pin "1") (pinfunction "I_1") (pintype "input"))
      (node (ref "E31") (pin "12") (pinfunction "1_12") (pintype "output"))
    )
    (net (code "258") (name "~{R_FEED_SW}") (class "Default")
      (node (ref "C63") (pin "1") (pinfunction "1_1") (pintype "passive"))
      (node (ref "E5") (pin "13") (pinfunction "I1_13") (pintype "input"))
      (node (ref "E6") (pin "1") (pinfunction "I0_1") (pintype "input"))
      (node (ref "J2") (pin "TT") (pinfunction "P_TT") (pintype "passive"))
      (node (ref "R49") (pin "1") (pinfunction "1_1") (pintype "passive"))
    )
    (net (code "259") (name "~{R_OFFLINE}") (class "Default")
      (node (ref "C51") (pin "1") (pinfunction "1_1") (pintype "passive"))
      (node (ref "E23") (pin "10") (pinfunction "I1_10") (pintype "input"))
      (node (ref "J2") (pin "F") (pinfunction "P_F") (pintype "passive"))
      (node (ref "R6") (pin "2") (pinfunction "2_2") (pintype "passive"))
    )
    (net (code "260") (name "~{SHIFT_PULSE}") (class "Default")
      (node (ref "E1") (pin "6") (pinfunction "O_6") (pintype "output"))
      (node (ref "E12") (pin "4") (pinfunction "PRE_4") (pintype "input"))
      (node (ref "E6") (pin "5") (pinfunction "I1_5") (pintype "input"))
    )
    (net (code "261") (name "~{SKIP}") (class "Default")
      (node (ref "E18") (pin "1") (pinfunction "O_1") (pintype "open_collector"))
      (node (ref "E18") (pin "4") (pinfunction "O_4") (pintype "open_collector"))
      (node (ref "OMNIBUS") (pin "CS1") (pinfunction "1_CS1") (pintype "bidirectional"))
    )
  )
)
